# DP_current_measure_v2.net
KiCad netlist of a schematic drawn in EAGLE
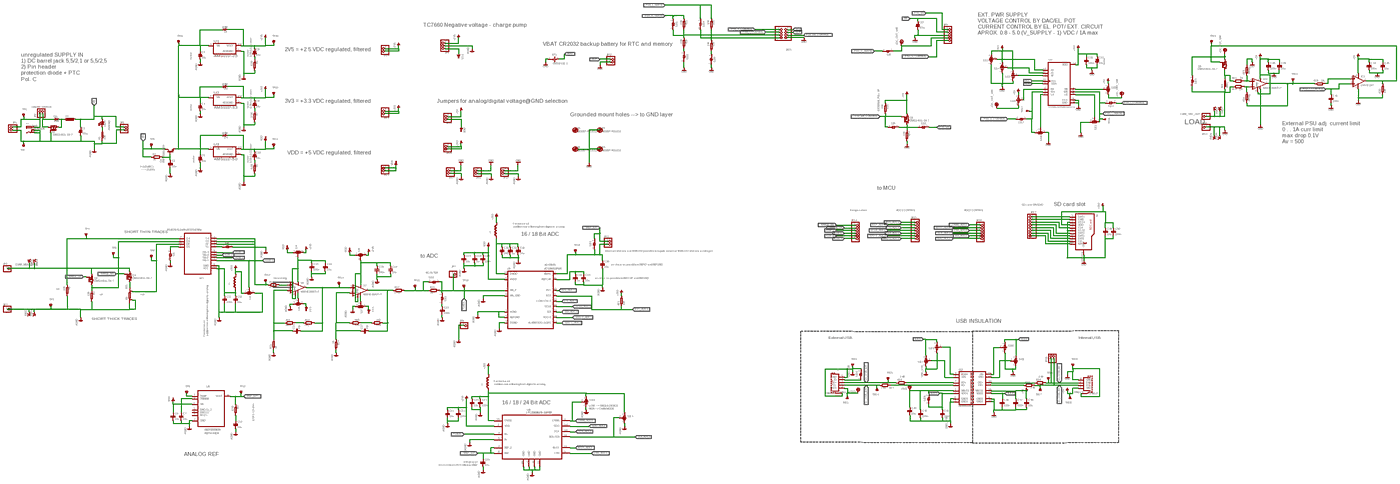
[diagram p0: schematic, sheet 1, overview]
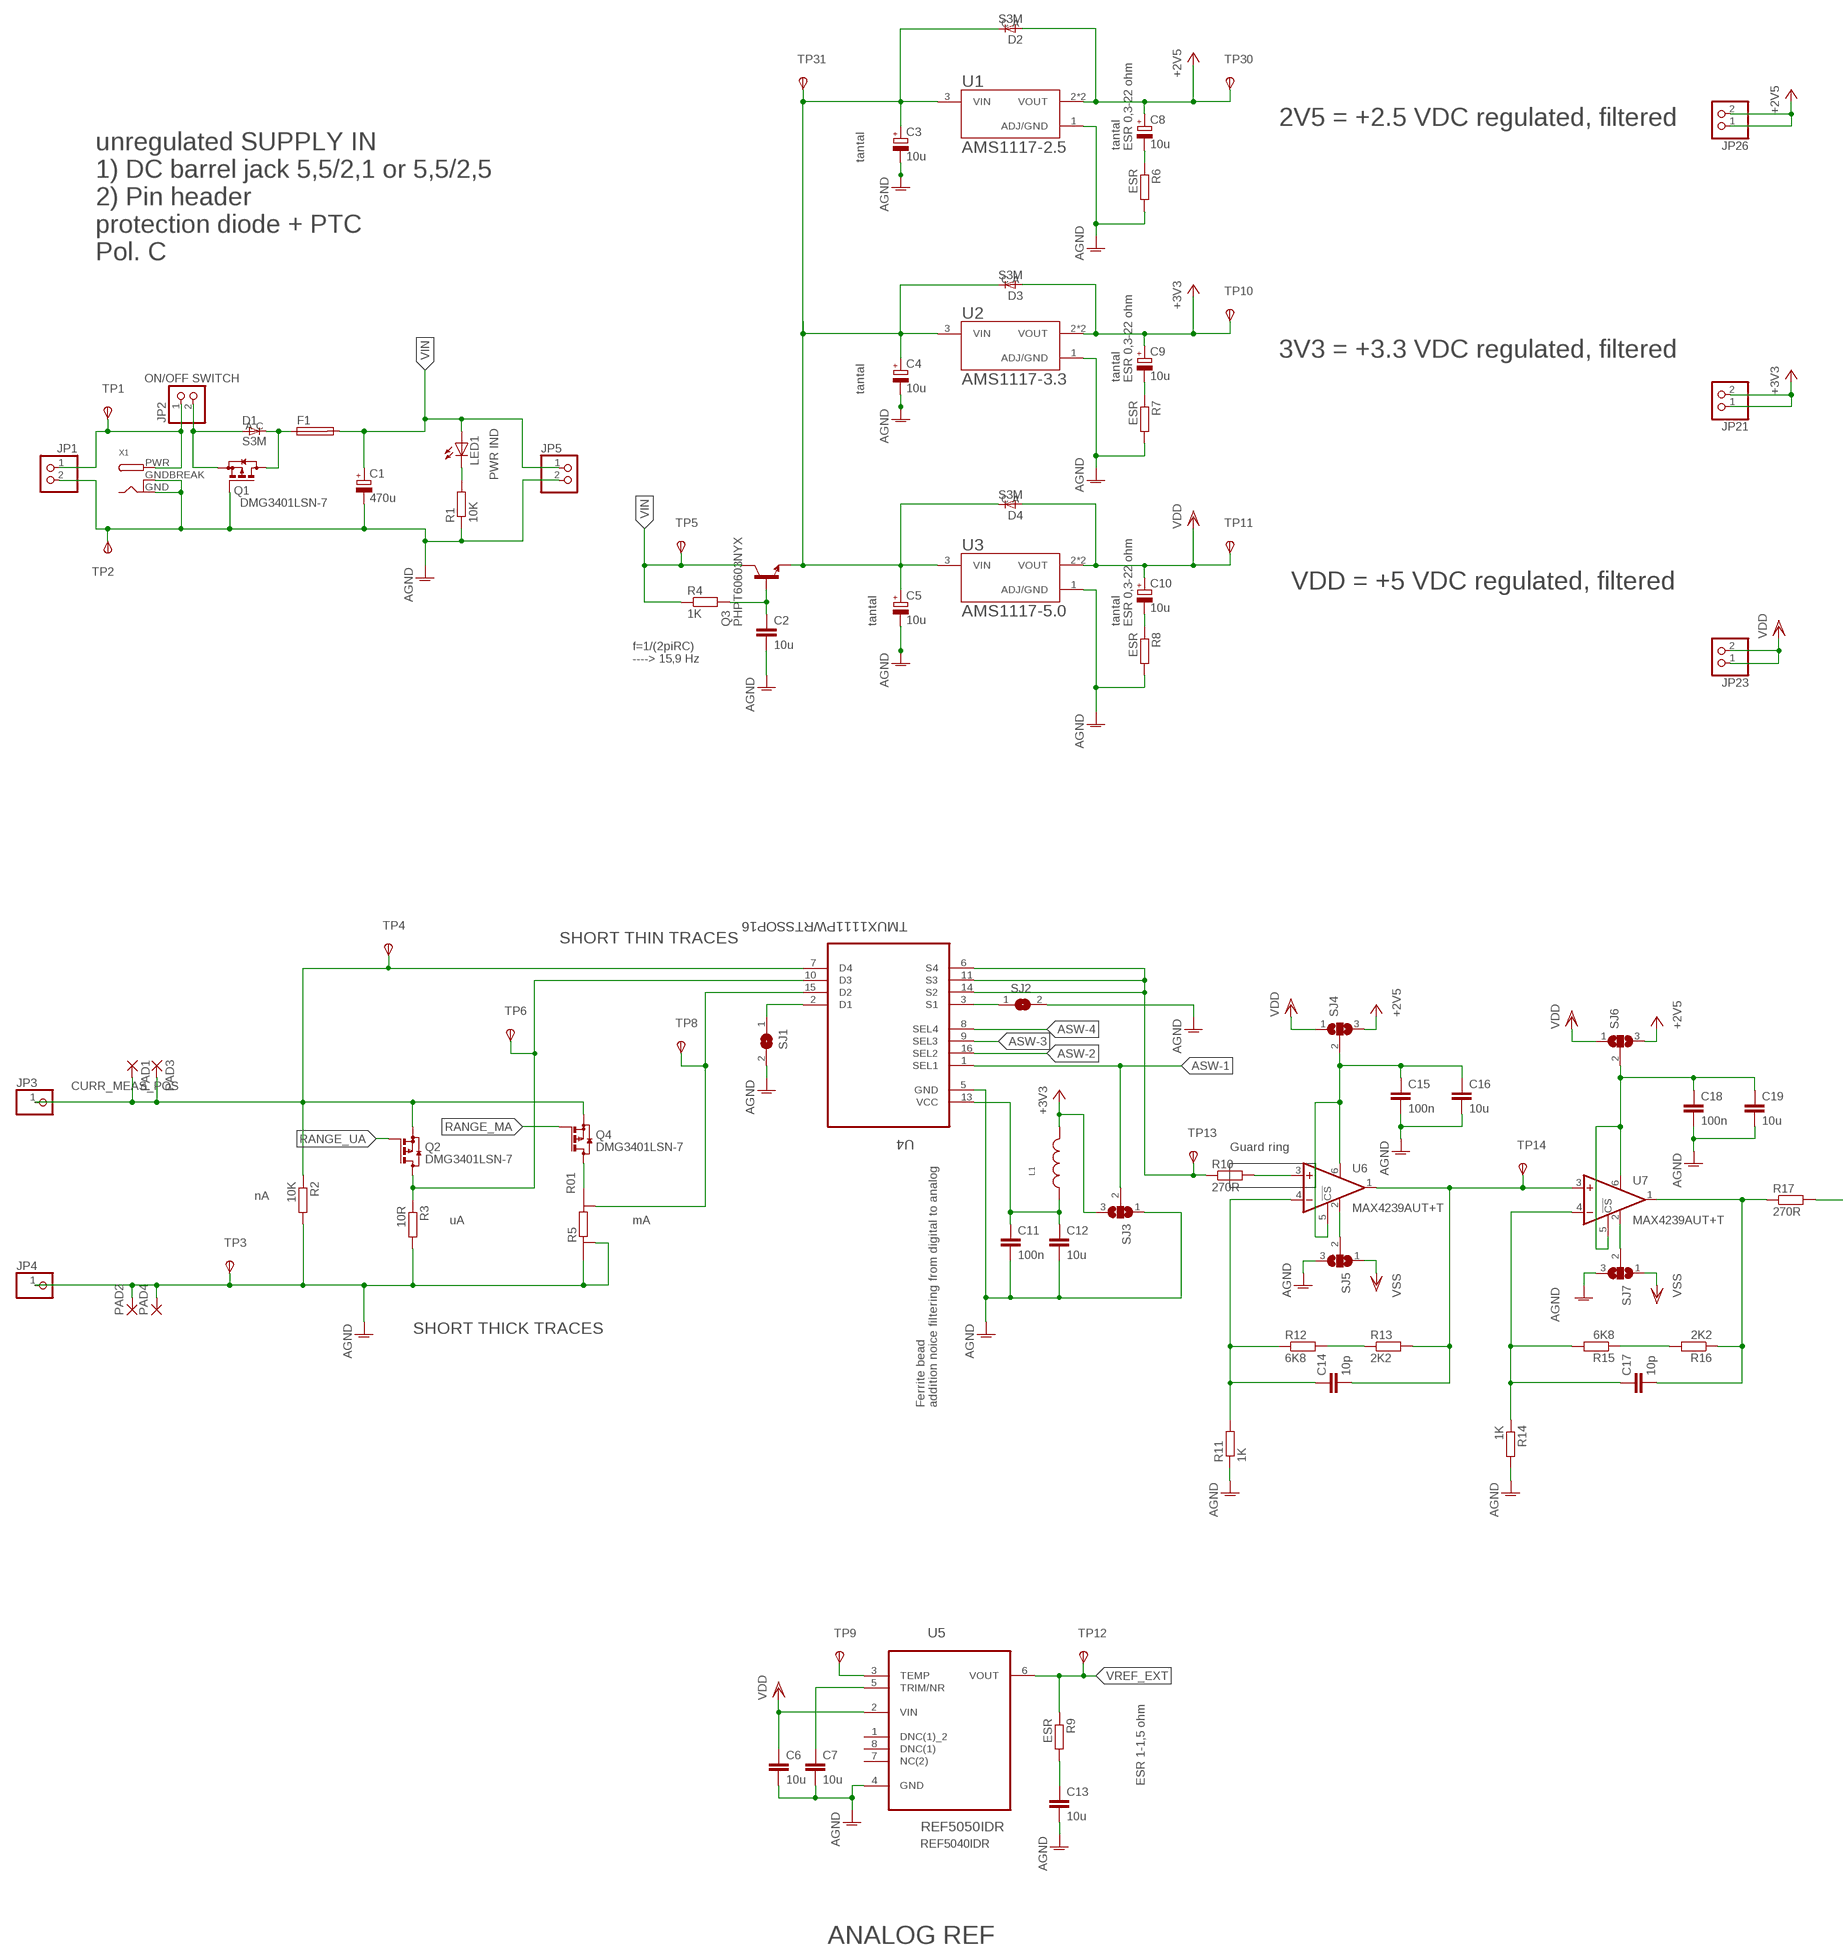
[diagram p1: schematic, sheet 1, part 1 of 4]
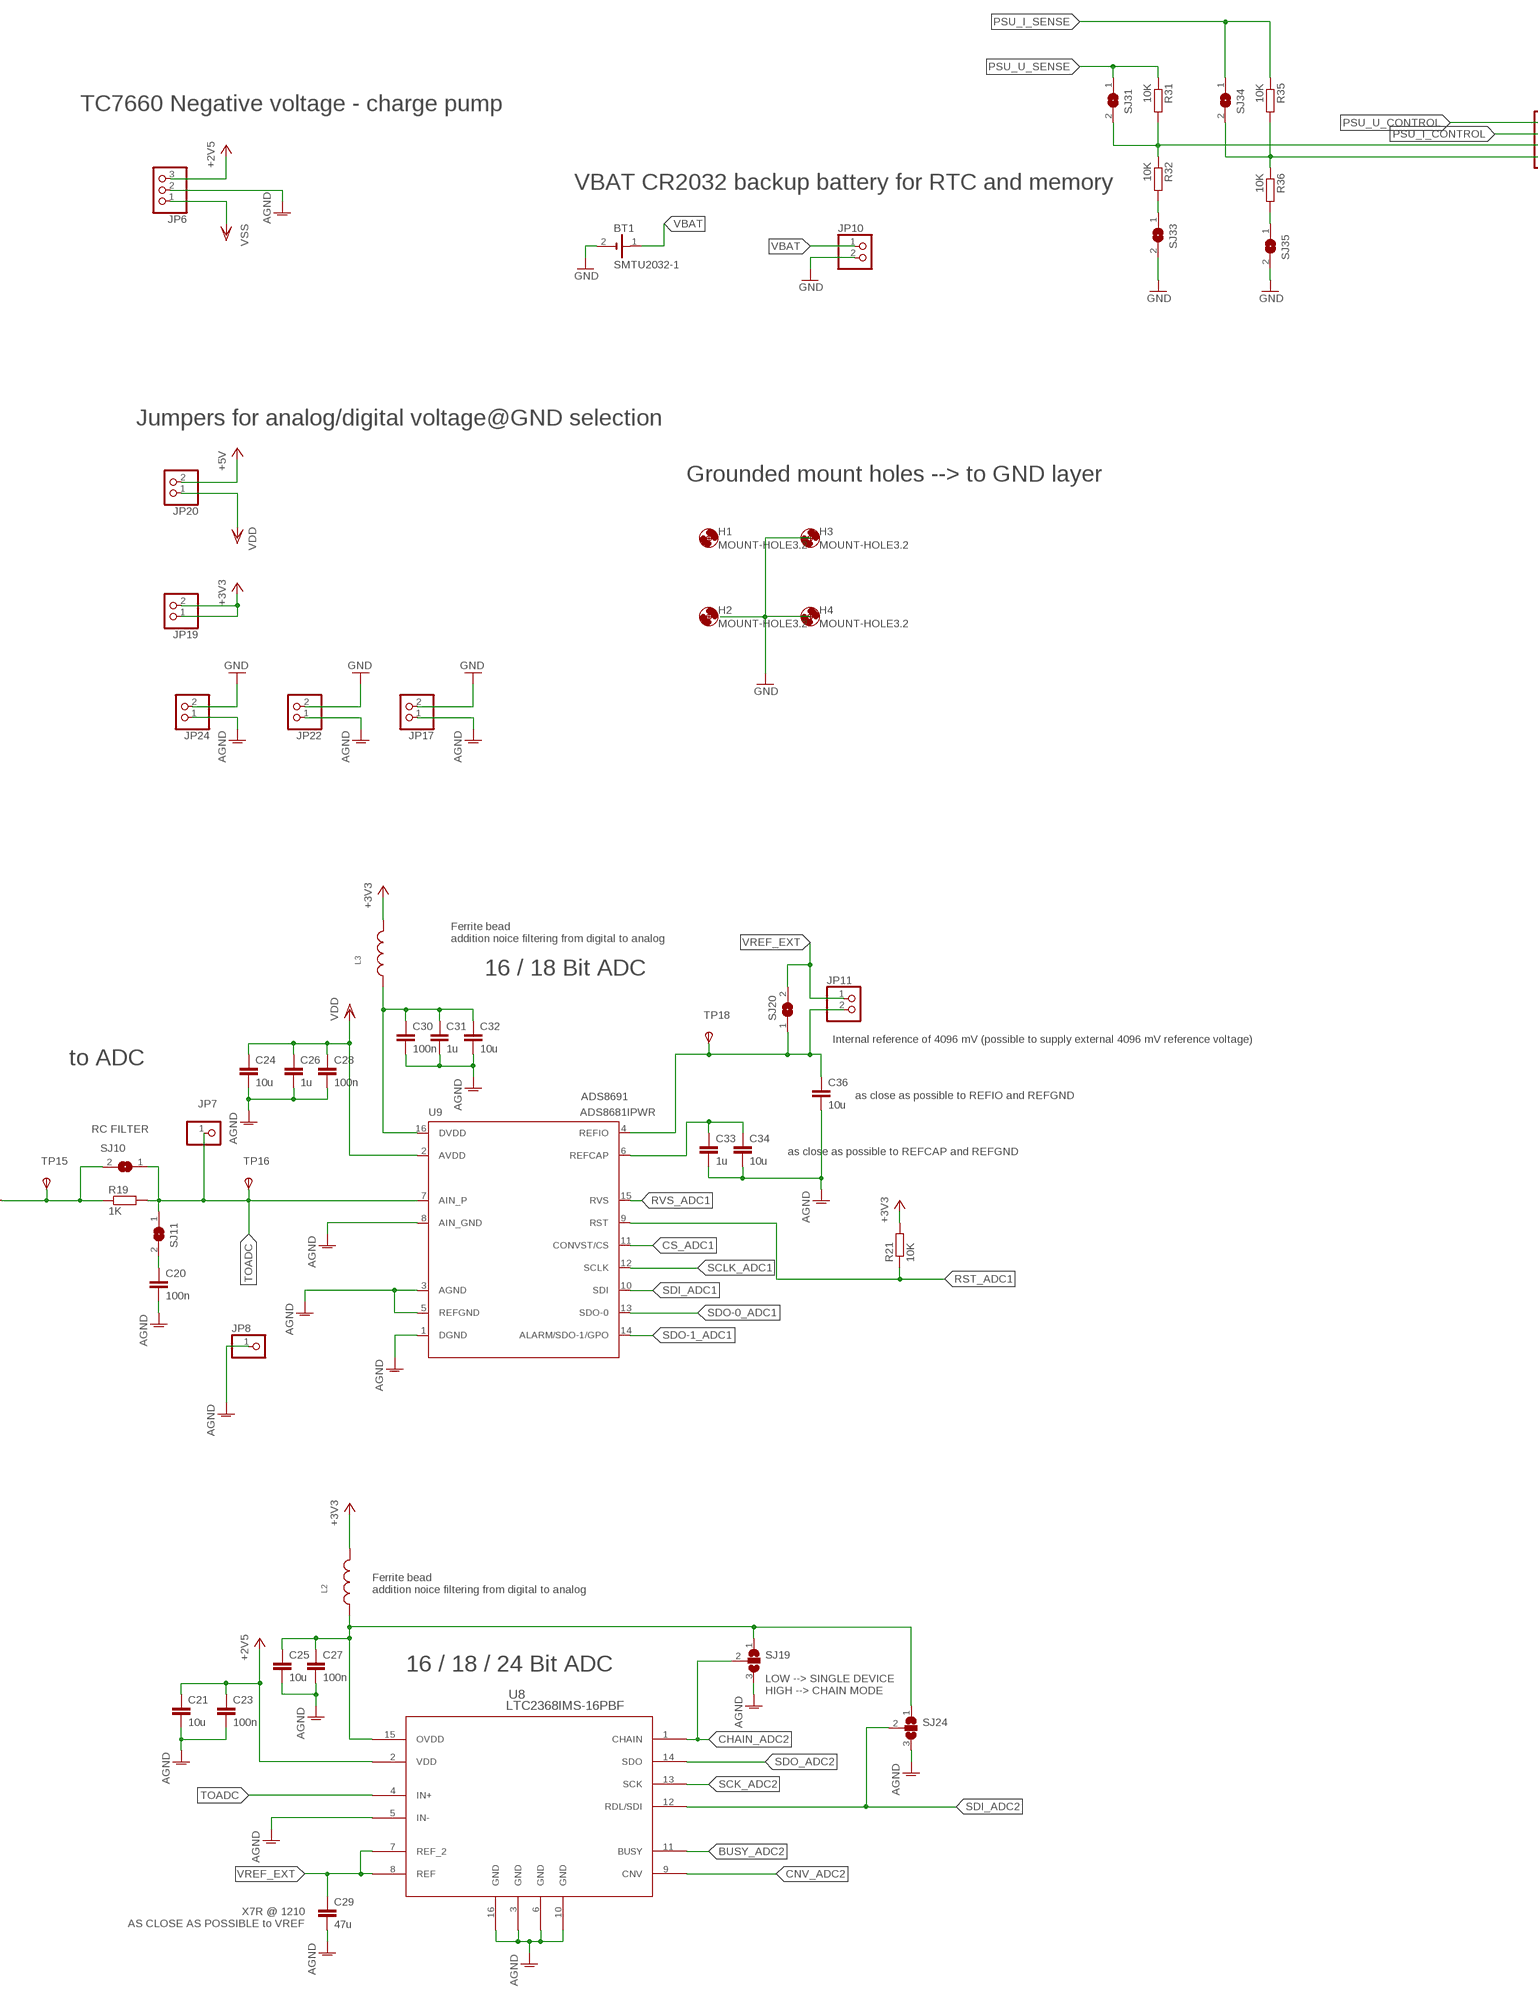
[diagram p2: schematic, sheet 1, part 2 of 4]
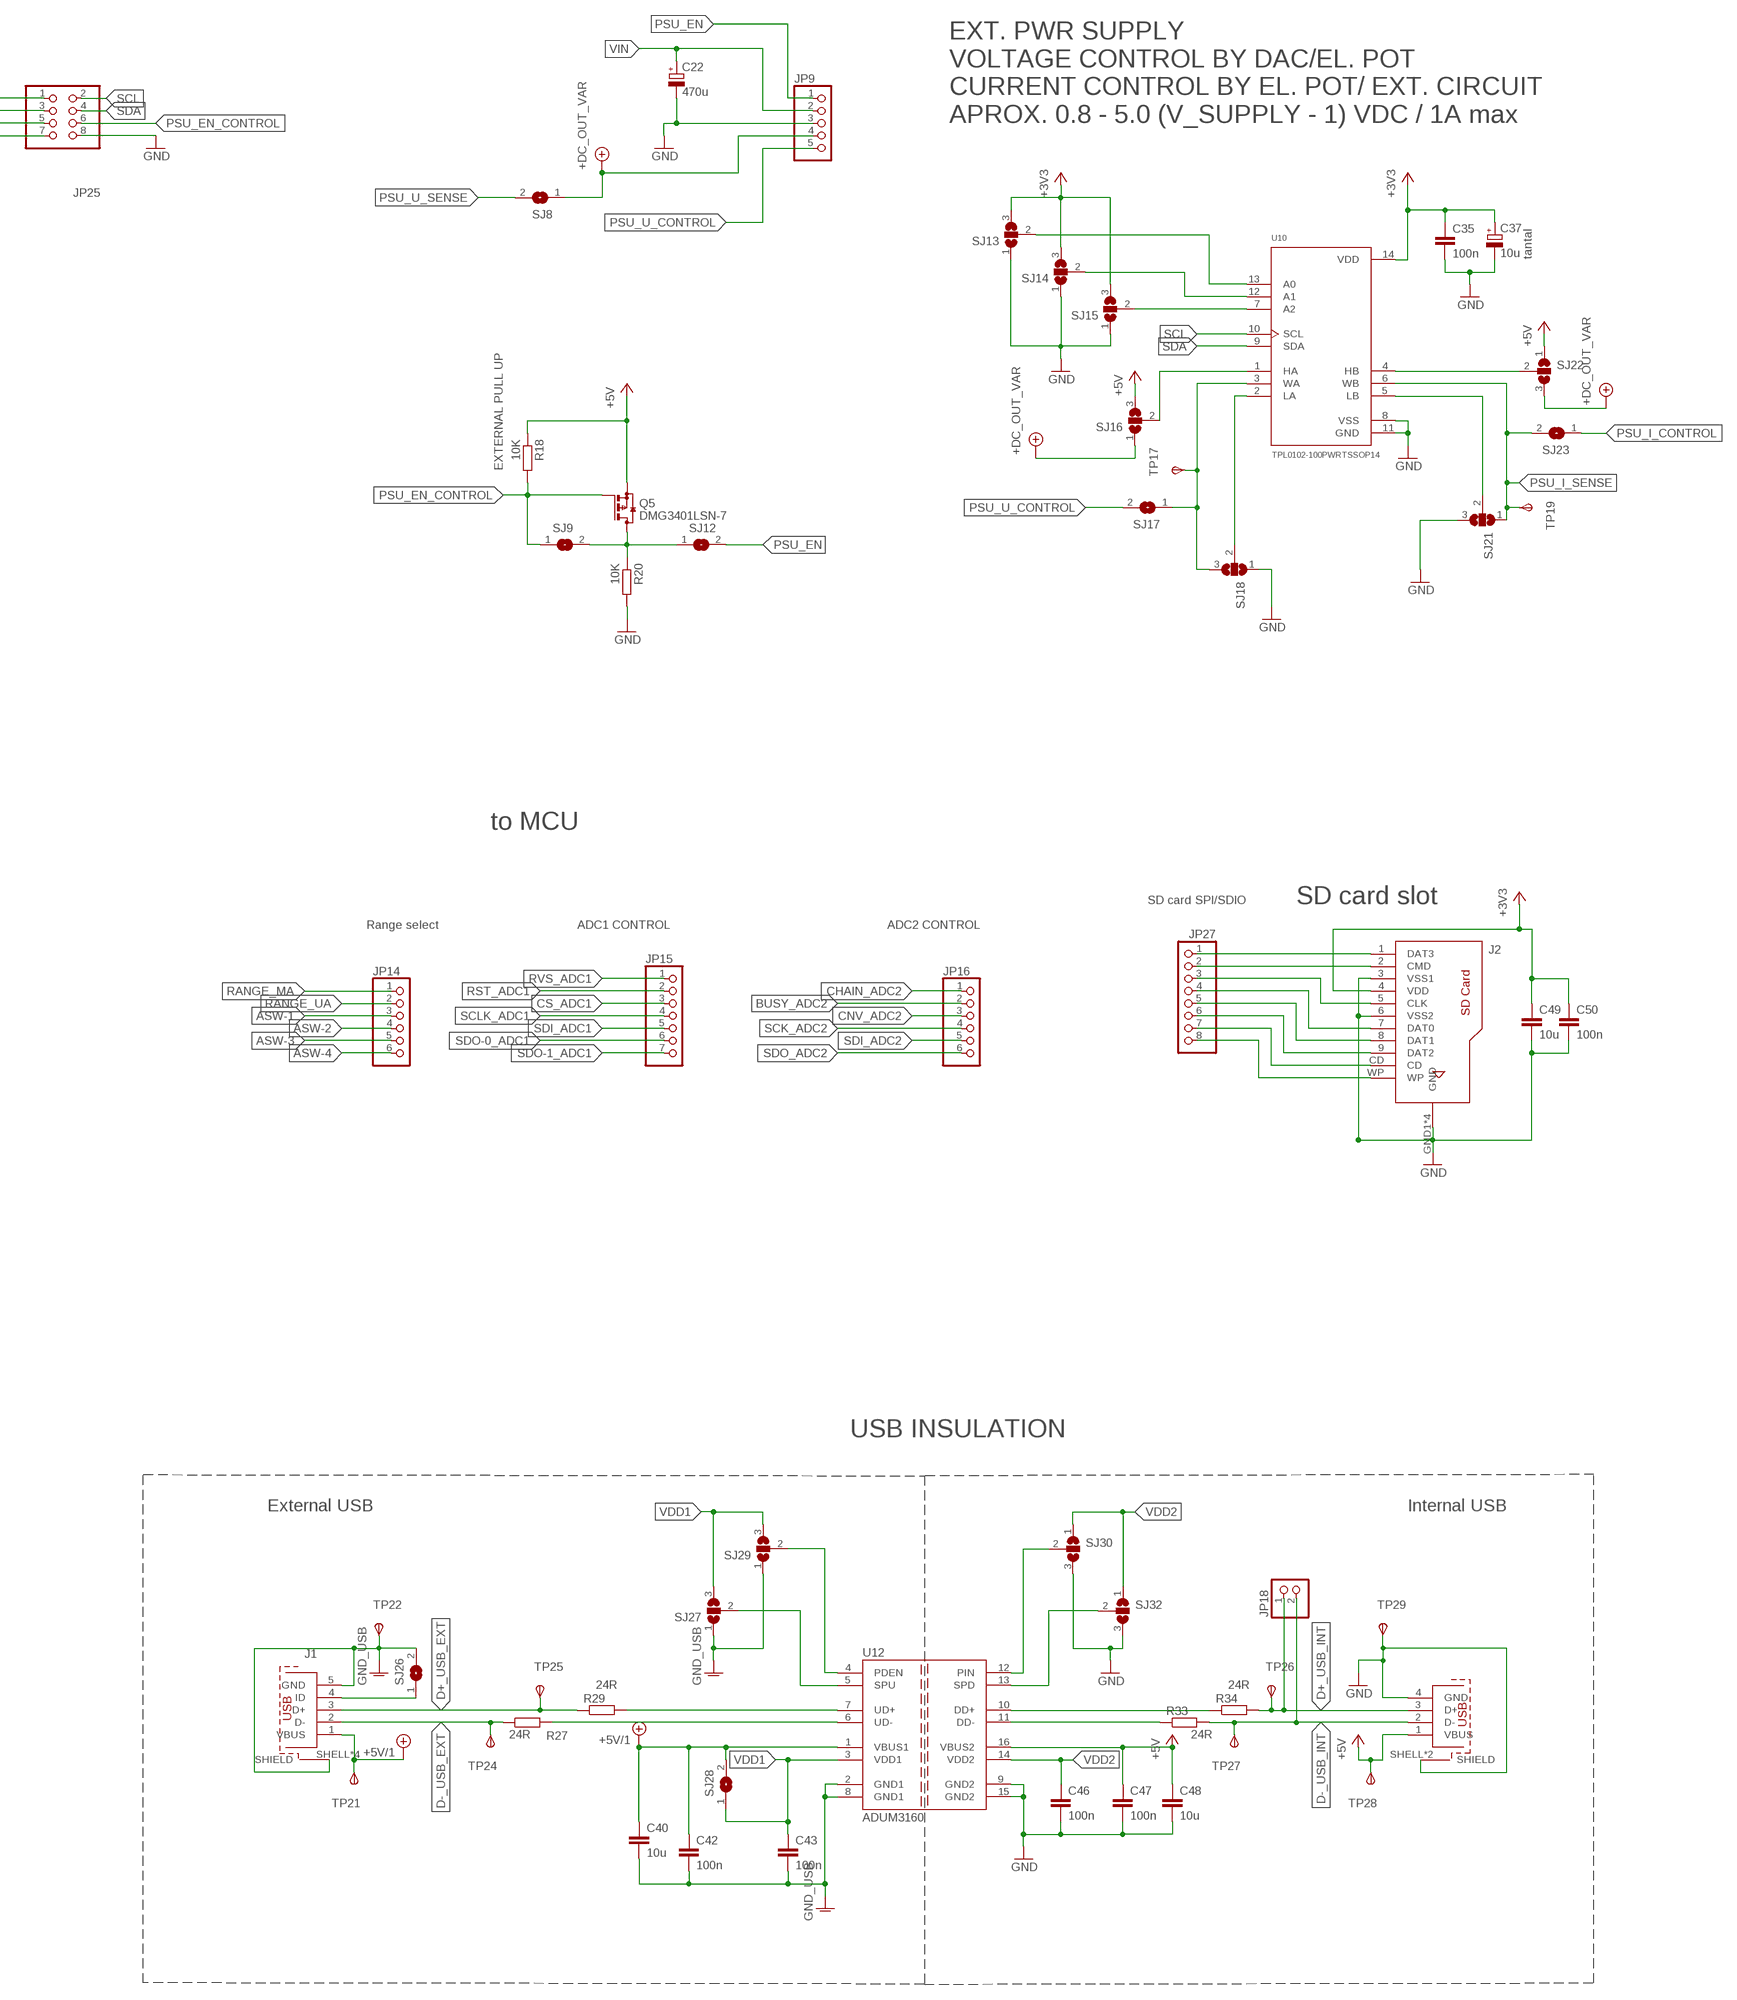
[diagram p3: schematic, sheet 1, part 3 of 4]
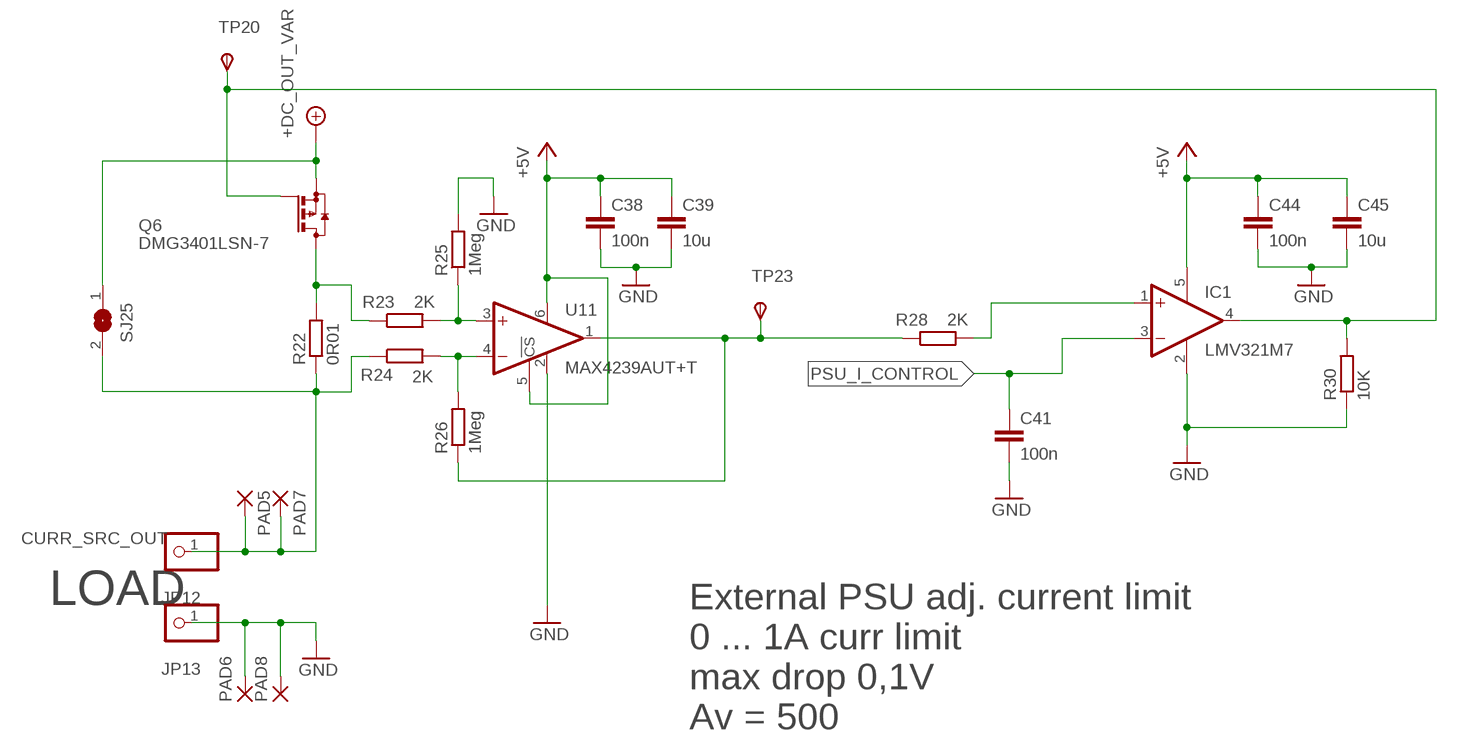
[diagram p4: schematic, sheet 1, part 4 of 4]

(export (version "E")
  (design (tool "Eeschema 10.0.6"))
  (components
    (comp (ref "BT1")
      (value "SMTU2032-1")
      (footprint "eagle-import:RENATA_SMTU2032-1")
      (fields (field (name "MF") "Renata"))
      (libsource (lib "eagle-import") (part "SMTU2032-1"))
    )
    (comp (ref "C1")
      (value "470u")
      (footprint "eagle-import:PANASONIC_G")
      (libsource (lib "eagle-import") (part "CPOL-EUG"))
    )
    (comp (ref "C2")
      (value "10u")
      (footprint "eagle-import:C1206")
      (libsource (lib "eagle-import") (part "C-EUC1206"))
    )
    (comp (ref "C3")
      (value "10u")
      (footprint "eagle-import:SMC_B")
      (libsource (lib "eagle-import") (part "CPOL-EUSMCB"))
    )
    (comp (ref "C4")
      (value "10u")
      (footprint "eagle-import:SMC_B")
      (libsource (lib "eagle-import") (part "CPOL-EUSMCB"))
    )
    (comp (ref "C5")
      (value "10u")
      (footprint "eagle-import:SMC_B")
      (libsource (lib "eagle-import") (part "CPOL-EUSMCB"))
    )
    (comp (ref "C6")
      (value "10u")
      (footprint "eagle-import:C1206")
      (libsource (lib "eagle-import") (part "C-EUC1206"))
    )
    (comp (ref "C7")
      (value "10u")
      (footprint "eagle-import:C1206")
      (libsource (lib "eagle-import") (part "C-EUC1206"))
    )
    (comp (ref "C8")
      (value "10u")
      (footprint "eagle-import:SMC_B")
      (libsource (lib "eagle-import") (part "CPOL-EUSMCB"))
    )
    (comp (ref "C9")
      (value "10u")
      (footprint "eagle-import:SMC_B")
      (libsource (lib "eagle-import") (part "CPOL-EUSMCB"))
    )
    (comp (ref "C10")
      (value "10u")
      (footprint "eagle-import:SMC_B")
      (libsource (lib "eagle-import") (part "CPOL-EUSMCB"))
    )
    (comp (ref "C11")
      (value "100n")
      (footprint "eagle-import:C0805")
      (libsource (lib "eagle-import") (part "C-EUC0805"))
    )
    (comp (ref "C12")
      (value "10u")
      (footprint "eagle-import:C1206")
      (libsource (lib "eagle-import") (part "C-EUC1206"))
    )
    (comp (ref "C13")
      (value "10u")
      (footprint "eagle-import:C1206")
      (libsource (lib "eagle-import") (part "C-EUC1206"))
    )
    (comp (ref "C14")
      (value "10p")
      (footprint "eagle-import:C0805")
      (libsource (lib "eagle-import") (part "C-EUC0805"))
    )
    (comp (ref "C15")
      (value "100n")
      (footprint "eagle-import:C0805")
      (libsource (lib "eagle-import") (part "C-EUC0805"))
    )
    (comp (ref "C16")
      (value "10u")
      (footprint "eagle-import:C1206")
      (libsource (lib "eagle-import") (part "C-EUC1206"))
    )
    (comp (ref "C17")
      (value "10p")
      (footprint "eagle-import:C0805")
      (libsource (lib "eagle-import") (part "C-EUC0805"))
    )
    (comp (ref "C18")
      (value "100n")
      (footprint "eagle-import:C0805")
      (libsource (lib "eagle-import") (part "C-EUC0805"))
    )
    (comp (ref "C19")
      (value "10u")
      (footprint "eagle-import:C1206")
      (libsource (lib "eagle-import") (part "C-EUC1206"))
    )
    (comp (ref "C20")
      (value "100n")
      (footprint "eagle-import:C1206")
      (libsource (lib "eagle-import") (part "C-EUC1206"))
    )
    (comp (ref "C21")
      (value "10u")
      (footprint "eagle-import:C1206")
      (libsource (lib "eagle-import") (part "C-EUC1206"))
    )
    (comp (ref "C22")
      (value "470u")
      (footprint "eagle-import:PANASONIC_G")
      (libsource (lib "eagle-import") (part "CPOL-EUG"))
    )
    (comp (ref "C23")
      (value "100n")
      (footprint "eagle-import:C0805")
      (libsource (lib "eagle-import") (part "C-EUC0805"))
    )
    (comp (ref "C24")
      (value "10u")
      (footprint "eagle-import:C1206")
      (libsource (lib "eagle-import") (part "C-EUC1206"))
    )
    (comp (ref "C25")
      (value "10u")
      (footprint "eagle-import:C1206")
      (libsource (lib "eagle-import") (part "C-EUC1206"))
    )
    (comp (ref "C26")
      (value "1u")
      (footprint "eagle-import:C0805")
      (libsource (lib "eagle-import") (part "C-EUC0805"))
    )
    (comp (ref "C27")
      (value "100n")
      (footprint "eagle-import:C0805")
      (libsource (lib "eagle-import") (part "C-EUC0805"))
    )
    (comp (ref "C28")
      (value "100n")
      (footprint "eagle-import:C0805")
      (libsource (lib "eagle-import") (part "C-EUC0805"))
    )
    (comp (ref "C29")
      (value "47u")
      (footprint "eagle-import:C1210")
      (libsource (lib "eagle-import") (part "C-EUC1210"))
    )
    (comp (ref "C30")
      (value "100n")
      (footprint "eagle-import:C0805")
      (libsource (lib "eagle-import") (part "C-EUC0805"))
    )
    (comp (ref "C31")
      (value "1u")
      (footprint "eagle-import:C0805")
      (libsource (lib "eagle-import") (part "C-EUC0805"))
    )
    (comp (ref "C32")
      (value "10u")
      (footprint "eagle-import:C1206")
      (libsource (lib "eagle-import") (part "C-EUC1206"))
    )
    (comp (ref "C33")
      (value "1u")
      (footprint "eagle-import:C0805")
      (libsource (lib "eagle-import") (part "C-EUC0805"))
    )
    (comp (ref "C34")
      (value "10u")
      (footprint "eagle-import:C1206")
      (libsource (lib "eagle-import") (part "C-EUC1206"))
    )
    (comp (ref "C35")
      (value "100n")
      (footprint "eagle-import:C0805")
      (libsource (lib "eagle-import") (part "C-EUC0805"))
    )
    (comp (ref "C36")
      (value "10u")
      (footprint "eagle-import:C1206")
      (libsource (lib "eagle-import") (part "C-EUC1206"))
    )
    (comp (ref "C37")
      (value "10u")
      (footprint "eagle-import:SMC_B")
      (libsource (lib "eagle-import") (part "CPOL-EUSMCB"))
    )
    (comp (ref "C38")
      (value "100n")
      (footprint "eagle-import:C0805")
      (libsource (lib "eagle-import") (part "C-EUC0805"))
    )
    (comp (ref "C39")
      (value "10u")
      (footprint "eagle-import:C1206")
      (libsource (lib "eagle-import") (part "C-EUC1206"))
    )
    (comp (ref "C40")
      (value "10u")
      (footprint "eagle-import:C1206")
      (libsource (lib "eagle-import") (part "C-EUC1206"))
    )
    (comp (ref "C41")
      (value "100n")
      (footprint "eagle-import:C0805")
      (libsource (lib "eagle-import") (part "C-EUC0805"))
    )
    (comp (ref "C42")
      (value "100n")
      (footprint "eagle-import:C0805")
      (libsource (lib "eagle-import") (part "C-EUC0805"))
    )
    (comp (ref "C43")
      (value "100n")
      (footprint "eagle-import:C0805")
      (libsource (lib "eagle-import") (part "C-EUC0805"))
    )
    (comp (ref "C44")
      (value "100n")
      (footprint "eagle-import:C0805")
      (libsource (lib "eagle-import") (part "C-EUC0805"))
    )
    (comp (ref "C45")
      (value "10u")
      (footprint "eagle-import:C1206")
      (libsource (lib "eagle-import") (part "C-EUC1206"))
    )
    (comp (ref "C46")
      (value "100n")
      (footprint "eagle-import:C0805")
      (libsource (lib "eagle-import") (part "C-EUC0805"))
    )
    (comp (ref "C47")
      (value "100n")
      (footprint "eagle-import:C0805")
      (libsource (lib "eagle-import") (part "C-EUC0805"))
    )
    (comp (ref "C48")
      (value "10u")
      (footprint "eagle-import:C1206")
      (libsource (lib "eagle-import") (part "C-EUC1206"))
    )
    (comp (ref "C49")
      (value "10u")
      (footprint "eagle-import:C1206")
      (libsource (lib "eagle-import") (part "C-EUC1206"))
    )
    (comp (ref "C50")
      (value "100n")
      (footprint "eagle-import:C0805")
      (libsource (lib "eagle-import") (part "C-EUC0805"))
    )
    (comp (ref "D1")
      (value "S3M")
      (footprint "eagle-import:DO214AC")
      (libsource (lib "eagle-import") (part "S1M"))
    )
    (comp (ref "D2")
      (value "S3M")
      (footprint "eagle-import:DO214AC")
      (libsource (lib "eagle-import") (part "S1M"))
    )
    (comp (ref "D3")
      (value "S3M")
      (footprint "eagle-import:DO214AC")
      (libsource (lib "eagle-import") (part "S1M"))
    )
    (comp (ref "D4")
      (value "S3M")
      (footprint "eagle-import:DO214AC")
      (libsource (lib "eagle-import") (part "S1M"))
    )
    (comp (ref "F1")
      (value "MF-MSMF050-2")
      (footprint "eagle-import:1812")
      (fields
        (field (name "DIGIKEY_PART_NUMBER") "MF-MSMF050-2TR-ND")
        (field (name "MANUFACTURER") "Bourns Inc.")
        (field (name "CREATED_BY") "PCBLayout.com")
      )
      (libsource (lib "eagle-import") (part "MF-MSMF050-2"))
    )
    (comp (ref "H1")
      (value "MOUNT-HOLE3.2")
      (footprint "eagle-import:3,2")
      (libsource (lib "eagle-import") (part "MOUNT-HOLE3.2"))
    )
    (comp (ref "H2")
      (value "MOUNT-HOLE3.2")
      (footprint "eagle-import:3,2")
      (libsource (lib "eagle-import") (part "MOUNT-HOLE3.2"))
    )
    (comp (ref "H3")
      (value "MOUNT-HOLE3.2")
      (footprint "eagle-import:3,2")
      (libsource (lib "eagle-import") (part "MOUNT-HOLE3.2"))
    )
    (comp (ref "H4")
      (value "MOUNT-HOLE3.2")
      (footprint "eagle-import:3,2")
      (libsource (lib "eagle-import") (part "MOUNT-HOLE3.2"))
    )
    (comp (ref "IC1")
      (value "LMV321M7")
      (footprint "eagle-import:SC70-5L")
      (libsource (lib "eagle-import") (part "LMV321?M7"))
    )
    (comp (ref "J1")
      (value "629105150521")
      (footprint "eagle-import:629105150521")
      (libsource (lib "eagle-import") (part "629105150521"))
    )
    (comp (ref "J2")
      (value "693063020911")
      (footprint "eagle-import:693063020911")
      (libsource (lib "eagle-import") (part "693063020911"))
    )
    (comp (ref "J3")
      (value "614004185023")
      (footprint "eagle-import:614004185023")
      (libsource (lib "eagle-import") (part "614004185023"))
    )
    (comp (ref "JP1")
      (value "PINHD-1X2")
      (footprint "eagle-import:1X02")
      (libsource (lib "eagle-import") (part "PINHD-1X2"))
    )
    (comp (ref "JP2")
      (value "PINHD-1X2")
      (footprint "eagle-import:1X02")
      (libsource (lib "eagle-import") (part "PINHD-1X2"))
    )
    (comp (ref "JP3")
      (value "PINHD-1X1")
      (footprint "eagle-import:1X01")
      (libsource (lib "eagle-import") (part "PINHD-1X1"))
    )
    (comp (ref "JP4")
      (value "PINHD-1X1")
      (footprint "eagle-import:1X01")
      (libsource (lib "eagle-import") (part "PINHD-1X1"))
    )
    (comp (ref "JP5")
      (value "PINHD-1X2")
      (footprint "eagle-import:1X02")
      (libsource (lib "eagle-import") (part "PINHD-1X2"))
    )
    (comp (ref "JP6")
      (value "PINHD-1X3")
      (footprint "eagle-import:1X03")
      (libsource (lib "eagle-import") (part "PINHD-1X3"))
    )
    (comp (ref "JP7")
      (value "PINHD-1X1")
      (footprint "eagle-import:1X01")
      (libsource (lib "eagle-import") (part "PINHD-1X1"))
    )
    (comp (ref "JP8")
      (value "PINHD-1X1")
      (footprint "eagle-import:1X01")
      (libsource (lib "eagle-import") (part "PINHD-1X1"))
    )
    (comp (ref "JP9")
      (value "PSU_STEP_DOWN")
      (footprint "eagle-import:1X05")
      (libsource (lib "eagle-import") (part "PSU_STEP_DOWN"))
    )
    (comp (ref "JP10")
      (value "PINHD-1X2")
      (footprint "eagle-import:1X02")
      (libsource (lib "eagle-import") (part "PINHD-1X2"))
    )
    (comp (ref "JP11")
      (value "PINHD-1X2")
      (footprint "eagle-import:1X02")
      (libsource (lib "eagle-import") (part "PINHD-1X2"))
    )
    (comp (ref "JP12")
      (value "PINHD-1X1")
      (footprint "eagle-import:1X01")
      (libsource (lib "eagle-import") (part "PINHD-1X1"))
    )
    (comp (ref "JP13")
      (value "PINHD-1X1")
      (footprint "eagle-import:1X01")
      (libsource (lib "eagle-import") (part "PINHD-1X1"))
    )
    (comp (ref "JP14")
      (value "PINHD-1X6")
      (footprint "eagle-import:1X06")
      (libsource (lib "eagle-import") (part "PINHD-1X6"))
    )
    (comp (ref "JP15")
      (value "PINHD-1X7")
      (footprint "eagle-import:1X07")
      (libsource (lib "eagle-import") (part "PINHD-1X7"))
    )
    (comp (ref "JP16")
      (value "PINHD-1X6")
      (footprint "eagle-import:1X06")
      (libsource (lib "eagle-import") (part "PINHD-1X6"))
    )
    (comp (ref "JP17")
      (value "PINHD-1X2")
      (footprint "eagle-import:1X02")
      (libsource (lib "eagle-import") (part "PINHD-1X2"))
    )
    (comp (ref "JP18")
      (value "PINHD-1X2")
      (footprint "eagle-import:1X02")
      (libsource (lib "eagle-import") (part "PINHD-1X2"))
    )
    (comp (ref "JP19")
      (value "PINHD-1X2")
      (footprint "eagle-import:1X02")
      (libsource (lib "eagle-import") (part "PINHD-1X2"))
    )
    (comp (ref "JP20")
      (value "PINHD-1X2")
      (footprint "eagle-import:1X02")
      (libsource (lib "eagle-import") (part "PINHD-1X2"))
    )
    (comp (ref "JP21")
      (value "PINHD-1X2")
      (footprint "eagle-import:1X02")
      (libsource (lib "eagle-import") (part "PINHD-1X2"))
    )
    (comp (ref "JP22")
      (value "PINHD-1X2")
      (footprint "eagle-import:1X02")
      (libsource (lib "eagle-import") (part "PINHD-1X2"))
    )
    (comp (ref "JP23")
      (value "PINHD-1X2")
      (footprint "eagle-import:1X02")
      (libsource (lib "eagle-import") (part "PINHD-1X2"))
    )
    (comp (ref "JP24")
      (value "PINHD-1X2")
      (footprint "eagle-import:1X02")
      (libsource (lib "eagle-import") (part "PINHD-1X2"))
    )
    (comp (ref "JP25")
      (value "PINHD-2X4")
      (footprint "eagle-import:2X04")
      (libsource (lib "eagle-import") (part "PINHD-2X4"))
    )
    (comp (ref "JP26")
      (value "PINHD-1X2")
      (footprint "eagle-import:1X02")
      (libsource (lib "eagle-import") (part "PINHD-1X2"))
    )
    (comp (ref "JP27")
      (value "PINHD-1X8")
      (footprint "eagle-import:1X08")
      (libsource (lib "eagle-import") (part "PINHD-1X8"))
    )
    (comp (ref "L1")
      (value "WE-CBF_0805_742792036_WB_HS")
      (footprint "eagle-import:WE-CBF_0805(W=3.0)")
      (libsource (lib "eagle-import") (part "WE-CBF_0805_WB_HS_742792036"))
    )
    (comp (ref "L2")
      (value "WE-CBF_0805_742792036_WB_HS")
      (footprint "eagle-import:WE-CBF_0805(W=3.0)")
      (libsource (lib "eagle-import") (part "WE-CBF_0805_WB_HS_742792036"))
    )
    (comp (ref "L3")
      (value "WE-CBF_0805_742792036_WB_HS")
      (footprint "eagle-import:WE-CBF_0805(W=3.0)")
      (libsource (lib "eagle-import") (part "WE-CBF_0805_WB_HS_742792036"))
    )
    (comp (ref "LED1")
      (value "LEDCHIPLED_0805")
      (footprint "eagle-import:CHIPLED_0805")
      (libsource (lib "eagle-import") (part "LEDCHIPLED_0805"))
    )
    (comp (ref "PAD1")
      (value "WIREPADSMD2,54-5,08")
      (footprint "eagle-import:SMD2,54-5,08")
      (libsource (lib "eagle-import") (part "WIREPADSMD2,54-5,08"))
    )
    (comp (ref "PAD2")
      (value "WIREPADSMD2,54-5,08")
      (footprint "eagle-import:SMD2,54-5,08")
      (libsource (lib "eagle-import") (part "WIREPADSMD2,54-5,08"))
    )
    (comp (ref "PAD3")
      (value "WIREPADSMD2,54-5,08")
      (footprint "eagle-import:SMD2,54-5,08")
      (libsource (lib "eagle-import") (part "WIREPADSMD2,54-5,08"))
    )
    (comp (ref "PAD4")
      (value "WIREPADSMD2,54-5,08")
      (footprint "eagle-import:SMD2,54-5,08")
      (libsource (lib "eagle-import") (part "WIREPADSMD2,54-5,08"))
    )
    (comp (ref "PAD5")
      (value "WIREPADSMD2,54-5,08")
      (footprint "eagle-import:SMD2,54-5,08")
      (libsource (lib "eagle-import") (part "WIREPADSMD2,54-5,08"))
    )
    (comp (ref "PAD6")
      (value "WIREPADSMD2,54-5,08")
      (footprint "eagle-import:SMD2,54-5,08")
      (libsource (lib "eagle-import") (part "WIREPADSMD2,54-5,08"))
    )
    (comp (ref "PAD7")
      (value "WIREPADSMD2,54-5,08")
      (footprint "eagle-import:SMD2,54-5,08")
      (libsource (lib "eagle-import") (part "WIREPADSMD2,54-5,08"))
    )
    (comp (ref "PAD8")
      (value "WIREPADSMD2,54-5,08")
      (footprint "eagle-import:SMD2,54-5,08")
      (libsource (lib "eagle-import") (part "WIREPADSMD2,54-5,08"))
    )
    (comp (ref "Q1")
      (value "DMG3401LSN-7")
      (footprint "eagle-import:SOT23")
      (libsource (lib "eagle-import") (part "DMG3401LSN-7"))
    )
    (comp (ref "Q2")
      (value "DMG3401LSN-7")
      (footprint "eagle-import:SOT23")
      (libsource (lib "eagle-import") (part "DMG3401LSN-7"))
    )
    (comp (ref "Q3")
      (value "PHPT60603NYX")
      (footprint "eagle-import:TO127P600X120-5N")
      (libsource (lib "eagle-import") (part "PHPT60603NYX"))
    )
    (comp (ref "Q4")
      (value "DMG3401LSN-7")
      (footprint "eagle-import:SOT23")
      (libsource (lib "eagle-import") (part "DMG3401LSN-7"))
    )
    (comp (ref "Q5")
      (value "DMG3401LSN-7")
      (footprint "eagle-import:SOT23")
      (libsource (lib "eagle-import") (part "DMG3401LSN-7"))
    )
    (comp (ref "Q6")
      (value "DMG3401LSN-7")
      (footprint "eagle-import:SOT23")
      (libsource (lib "eagle-import") (part "DMG3401LSN-7"))
    )
    (comp (ref "R1")
      (value "10K")
      (footprint "eagle-import:R0805")
      (libsource (lib "eagle-import") (part "R-EU_R0805"))
    )
    (comp (ref "R2")
      (value "10K")
      (footprint "eagle-import:R0805")
      (libsource (lib "eagle-import") (part "R-EU_R0805"))
    )
    (comp (ref "R3")
      (value "10R")
      (footprint "eagle-import:R0805")
      (libsource (lib "eagle-import") (part "R-EU_R0805"))
    )
    (comp (ref "R4")
      (value "1K")
      (footprint "eagle-import:R0805")
      (libsource (lib "eagle-import") (part "R-EU_R0805"))
    )
    (comp (ref "R5")
      (value "R01")
      (footprint "eagle-import:R2512")
      (libsource (lib "eagle-import") (part "CSM_R01"))
    )
    (comp (ref "R6")
      (value "ESR")
      (footprint "eagle-import:R0805")
      (libsource (lib "eagle-import") (part "R-EU_R0805"))
    )
    (comp (ref "R7")
      (value "ESR")
      (footprint "eagle-import:R0805")
      (libsource (lib "eagle-import") (part "R-EU_R0805"))
    )
    (comp (ref "R8")
      (value "ESR")
      (footprint "eagle-import:R0805")
      (libsource (lib "eagle-import") (part "R-EU_R0805"))
    )
    (comp (ref "R9")
      (value "ESR")
      (footprint "eagle-import:R0805")
      (libsource (lib "eagle-import") (part "R-EU_R0805"))
    )
    (comp (ref "R10")
      (value "270R")
      (footprint "eagle-import:R0805")
      (libsource (lib "eagle-import") (part "R-EU_R0805"))
    )
    (comp (ref "R11")
      (value "1K")
      (footprint "eagle-import:R0805")
      (libsource (lib "eagle-import") (part "R-EU_R0805"))
    )
    (comp (ref "R12")
      (value "6K8")
      (footprint "eagle-import:R0805")
      (libsource (lib "eagle-import") (part "R-EU_R0805"))
    )
    (comp (ref "R13")
      (value "2K2")
      (footprint "eagle-import:R0805")
      (libsource (lib "eagle-import") (part "R-EU_R0805"))
    )
    (comp (ref "R14")
      (value "1K")
      (footprint "eagle-import:R0805")
      (libsource (lib "eagle-import") (part "R-EU_R0805"))
    )
    (comp (ref "R15")
      (value "6K8")
      (footprint "eagle-import:R0805")
      (libsource (lib "eagle-import") (part "R-EU_R0805"))
    )
    (comp (ref "R16")
      (value "2K2")
      (footprint "eagle-import:R0805")
      (libsource (lib "eagle-import") (part "R-EU_R0805"))
    )
    (comp (ref "R17")
      (value "270R")
      (footprint "eagle-import:R0805")
      (libsource (lib "eagle-import") (part "R-EU_R0805"))
    )
    (comp (ref "R18")
      (value "10K")
      (footprint "eagle-import:R0805")
      (libsource (lib "eagle-import") (part "R-EU_R0805"))
    )
    (comp (ref "R19")
      (value "1K")
      (footprint "eagle-import:R0805")
      (libsource (lib "eagle-import") (part "R-EU_R0805"))
    )
    (comp (ref "R20")
      (value "10K")
      (footprint "eagle-import:R0805")
      (libsource (lib "eagle-import") (part "R-EU_R0805"))
    )
    (comp (ref "R21")
      (value "10K")
      (footprint "eagle-import:R0805")
      (libsource (lib "eagle-import") (part "R-EU_R0805"))
    )
    (comp (ref "R22")
      (value "0R01")
      (footprint "eagle-import:R0805")
      (libsource (lib "eagle-import") (part "R-EU_R0805"))
    )
    (comp (ref "R23")
      (value "2K")
      (footprint "eagle-import:R0805")
      (libsource (lib "eagle-import") (part "R-EU_R0805"))
    )
    (comp (ref "R24")
      (value "2K")
      (footprint "eagle-import:R0805")
      (libsource (lib "eagle-import") (part "R-EU_R0805"))
    )
    (comp (ref "R25")
      (value "1Meg")
      (footprint "eagle-import:R0805")
      (libsource (lib "eagle-import") (part "R-EU_R0805"))
    )
    (comp (ref "R26")
      (value "1Meg")
      (footprint "eagle-import:R0805")
      (libsource (lib "eagle-import") (part "R-EU_R0805"))
    )
    (comp (ref "R27")
      (value "24R")
      (footprint "eagle-import:R0805")
      (libsource (lib "eagle-import") (part "R-EU_R0805"))
    )
    (comp (ref "R28")
      (value "2K")
      (footprint "eagle-import:R0805")
      (libsource (lib "eagle-import") (part "R-EU_R0805"))
    )
    (comp (ref "R29")
      (value "24R")
      (footprint "eagle-import:R0805")
      (libsource (lib "eagle-import") (part "R-EU_R0805"))
    )
    (comp (ref "R30")
      (value "10K")
      (footprint "eagle-import:R0805")
      (libsource (lib "eagle-import") (part "R-EU_R0805"))
    )
    (comp (ref "R31")
      (value "10K")
      (footprint "eagle-import:R0805")
      (libsource (lib "eagle-import") (part "R-EU_R0805"))
    )
    (comp (ref "R32")
      (value "10K")
      (footprint "eagle-import:R0805")
      (libsource (lib "eagle-import") (part "R-EU_R0805"))
    )
    (comp (ref "R33")
      (value "24R")
      (footprint "eagle-import:R0805")
      (libsource (lib "eagle-import") (part "R-EU_R0805"))
    )
    (comp (ref "R34")
      (value "24R")
      (footprint "eagle-import:R0805")
      (libsource (lib "eagle-import") (part "R-EU_R0805"))
    )
    (comp (ref "R35")
      (value "10K")
      (footprint "eagle-import:R0805")
      (libsource (lib "eagle-import") (part "R-EU_R0805"))
    )
    (comp (ref "R36")
      (value "10K")
      (footprint "eagle-import:R0805")
      (libsource (lib "eagle-import") (part "R-EU_R0805"))
    )
    (comp (ref "SJ1") (value "SJ") (footprint "eagle-import:SJ") (libsource (lib "eagle-import") (part "SJ")))
    (comp (ref "SJ2") (value "SJ") (footprint "eagle-import:SJ") (libsource (lib "eagle-import") (part "SJ")))
    (comp (ref "SJ3")
      (value "SJ2W")
      (footprint "eagle-import:SJ_2")
      (libsource (lib "eagle-import") (part "SJ2W"))
    )
    (comp (ref "SJ4")
      (value "SJ2W")
      (footprint "eagle-import:SJ_2")
      (libsource (lib "eagle-import") (part "SJ2W"))
    )
    (comp (ref "SJ5")
      (value "SJ2W")
      (footprint "eagle-import:SJ_2")
      (libsource (lib "eagle-import") (part "SJ2W"))
    )
    (comp (ref "SJ6")
      (value "SJ2W")
      (footprint "eagle-import:SJ_2")
      (libsource (lib "eagle-import") (part "SJ2W"))
    )
    (comp (ref "SJ7")
      (value "SJ2W")
      (footprint "eagle-import:SJ_2")
      (libsource (lib "eagle-import") (part "SJ2W"))
    )
    (comp (ref "SJ8") (value "SJ") (footprint "eagle-import:SJ") (libsource (lib "eagle-import") (part "SJ")))
    (comp (ref "SJ9") (value "SJ") (footprint "eagle-import:SJ") (libsource (lib "eagle-import") (part "SJ")))
    (comp (ref "SJ10")
      (value "SJ")
      (footprint "eagle-import:SJ")
      (libsource (lib "eagle-import") (part "SJ"))
    )
    (comp (ref "SJ11")
      (value "SJ")
      (footprint "eagle-import:SJ")
      (libsource (lib "eagle-import") (part "SJ"))
    )
    (comp (ref "SJ12")
      (value "SJ")
      (footprint "eagle-import:SJ")
      (libsource (lib "eagle-import") (part "SJ"))
    )
    (comp (ref "SJ13")
      (value "SJ2W")
      (footprint "eagle-import:SJ_2")
      (libsource (lib "eagle-import") (part "SJ2W"))
    )
    (comp (ref "SJ14")
      (value "SJ2W")
      (footprint "eagle-import:SJ_2")
      (libsource (lib "eagle-import") (part "SJ2W"))
    )
    (comp (ref "SJ15")
      (value "SJ2W")
      (footprint "eagle-import:SJ_2")
      (libsource (lib "eagle-import") (part "SJ2W"))
    )
    (comp (ref "SJ16")
      (value "SJ2W")
      (footprint "eagle-import:SJ_2")
      (libsource (lib "eagle-import") (part "SJ2W"))
    )
    (comp (ref "SJ17")
      (value "SJ")
      (footprint "eagle-import:SJ")
      (libsource (lib "eagle-import") (part "SJ"))
    )
    (comp (ref "SJ18")
      (value "SJ2W")
      (footprint "eagle-import:SJ_2")
      (libsource (lib "eagle-import") (part "SJ2W"))
    )
    (comp (ref "SJ19")
      (value "SJ2W")
      (footprint "eagle-import:SJ_2")
      (libsource (lib "eagle-import") (part "SJ2W"))
    )
    (comp (ref "SJ20")
      (value "SJ")
      (footprint "eagle-import:SJ")
      (libsource (lib "eagle-import") (part "SJ"))
    )
    (comp (ref "SJ21")
      (value "SJ2W")
      (footprint "eagle-import:SJ_2")
      (libsource (lib "eagle-import") (part "SJ2W"))
    )
    (comp (ref "SJ22")
      (value "SJ2W")
      (footprint "eagle-import:SJ_2")
      (libsource (lib "eagle-import") (part "SJ2W"))
    )
    (comp (ref "SJ23")
      (value "SJ")
      (footprint "eagle-import:SJ")
      (libsource (lib "eagle-import") (part "SJ"))
    )
    (comp (ref "SJ24")
      (value "SJ2W")
      (footprint "eagle-import:SJ_2")
      (libsource (lib "eagle-import") (part "SJ2W"))
    )
    (comp (ref "SJ25")
      (value "SJ")
      (footprint "eagle-import:SJ")
      (libsource (lib "eagle-import") (part "SJ"))
    )
    (comp (ref "SJ26")
      (value "SJ")
      (footprint "eagle-import:SJ")
      (libsource (lib "eagle-import") (part "SJ"))
    )
    (comp (ref "SJ27")
      (value "SJ2W")
      (footprint "eagle-import:SJ_2")
      (libsource (lib "eagle-import") (part "SJ2W"))
    )
    (comp (ref "SJ28")
      (value "SJ")
      (footprint "eagle-import:SJ")
      (libsource (lib "eagle-import") (part "SJ"))
    )
    (comp (ref "SJ29")
      (value "SJ2W")
      (footprint "eagle-import:SJ_2")
      (libsource (lib "eagle-import") (part "SJ2W"))
    )
    (comp (ref "SJ30")
      (value "SJ2W")
      (footprint "eagle-import:SJ_2")
      (libsource (lib "eagle-import") (part "SJ2W"))
    )
    (comp (ref "SJ31")
      (value "SJ")
      (footprint "eagle-import:SJ")
      (libsource (lib "eagle-import") (part "SJ"))
    )
    (comp (ref "SJ32")
      (value "SJ2W")
      (footprint "eagle-import:SJ_2")
      (libsource (lib "eagle-import") (part "SJ2W"))
    )
    (comp (ref "SJ33")
      (value "SJ")
      (footprint "eagle-import:SJ")
      (libsource (lib "eagle-import") (part "SJ"))
    )
    (comp (ref "SJ34")
      (value "SJ")
      (footprint "eagle-import:SJ")
      (libsource (lib "eagle-import") (part "SJ"))
    )
    (comp (ref "SJ35")
      (value "SJ")
      (footprint "eagle-import:SJ")
      (libsource (lib "eagle-import") (part "SJ"))
    )
    (comp (ref "TP1")
      (value "TPSB1,27")
      (footprint "eagle-import:B1,27")
      (libsource (lib "eagle-import") (part "TPSB1,27"))
    )
    (comp (ref "TP2")
      (value "TPSB1,27")
      (footprint "eagle-import:B1,27")
      (libsource (lib "eagle-import") (part "TPSB1,27"))
    )
    (comp (ref "TP3")
      (value "TPSB1,27")
      (footprint "eagle-import:B1,27")
      (libsource (lib "eagle-import") (part "TPSB1,27"))
    )
    (comp (ref "TP4")
      (value "TPSB1,27")
      (footprint "eagle-import:B1,27")
      (libsource (lib "eagle-import") (part "TPSB1,27"))
    )
    (comp (ref "TP5")
      (value "TPSB1,27")
      (footprint "eagle-import:B1,27")
      (libsource (lib "eagle-import") (part "TPSB1,27"))
    )
    (comp (ref "TP6")
      (value "TPSB1,27")
      (footprint "eagle-import:B1,27")
      (libsource (lib "eagle-import") (part "TPSB1,27"))
    )
    (comp (ref "TP8")
      (value "TPSB1,27")
      (footprint "eagle-import:B1,27")
      (libsource (lib "eagle-import") (part "TPSB1,27"))
    )
    (comp (ref "TP9")
      (value "TPSB1,27")
      (footprint "eagle-import:B1,27")
      (libsource (lib "eagle-import") (part "TPSB1,27"))
    )
    (comp (ref "TP10")
      (value "TPSB1,27")
      (footprint "eagle-import:B1,27")
      (libsource (lib "eagle-import") (part "TPSB1,27"))
    )
    (comp (ref "TP11")
      (value "TPSB1,27")
      (footprint "eagle-import:B1,27")
      (libsource (lib "eagle-import") (part "TPSB1,27"))
    )
    (comp (ref "TP12")
      (value "TPSB1,27")
      (footprint "eagle-import:B1,27")
      (libsource (lib "eagle-import") (part "TPSB1,27"))
    )
    (comp (ref "TP13")
      (value "TPSB1,27")
      (footprint "eagle-import:B1,27")
      (libsource (lib "eagle-import") (part "TPSB1,27"))
    )
    (comp (ref "TP14")
      (value "TPSB1,27")
      (footprint "eagle-import:B1,27")
      (libsource (lib "eagle-import") (part "TPSB1,27"))
    )
    (comp (ref "TP15")
      (value "TPSB1,27")
      (footprint "eagle-import:B1,27")
      (libsource (lib "eagle-import") (part "TPSB1,27"))
    )
    (comp (ref "TP16")
      (value "TPSB1,27")
      (footprint "eagle-import:B1,27")
      (libsource (lib "eagle-import") (part "TPSB1,27"))
    )
    (comp (ref "TP17")
      (value "TPSB1,27")
      (footprint "eagle-import:B1,27")
      (libsource (lib "eagle-import") (part "TPSB1,27"))
    )
    (comp (ref "TP18")
      (value "TPSB1,27")
      (footprint "eagle-import:B1,27")
      (libsource (lib "eagle-import") (part "TPSB1,27"))
    )
    (comp (ref "TP19")
      (value "TPSB1,27")
      (footprint "eagle-import:B1,27")
      (libsource (lib "eagle-import") (part "TPSB1,27"))
    )
    (comp (ref "TP20")
      (value "TPSB1,27")
      (footprint "eagle-import:B1,27")
      (libsource (lib "eagle-import") (part "TPSB1,27"))
    )
    (comp (ref "TP21")
      (value "TPSB1,27")
      (footprint "eagle-import:B1,27")
      (libsource (lib "eagle-import") (part "TPSB1,27"))
    )
    (comp (ref "TP22")
      (value "TPSB1,27")
      (footprint "eagle-import:B1,27")
      (libsource (lib "eagle-import") (part "TPSB1,27"))
    )
    (comp (ref "TP23")
      (value "TPSB1,27")
      (footprint "eagle-import:B1,27")
      (libsource (lib "eagle-import") (part "TPSB1,27"))
    )
    (comp (ref "TP24")
      (value "TPSB1,27")
      (footprint "eagle-import:B1,27")
      (libsource (lib "eagle-import") (part "TPSB1,27"))
    )
    (comp (ref "TP25")
      (value "TPSB1,27")
      (footprint "eagle-import:B1,27")
      (libsource (lib "eagle-import") (part "TPSB1,27"))
    )
    (comp (ref "TP26")
      (value "TPSB1,27")
      (footprint "eagle-import:B1,27")
      (libsource (lib "eagle-import") (part "TPSB1,27"))
    )
    (comp (ref "TP27")
      (value "TPSB1,27")
      (footprint "eagle-import:B1,27")
      (libsource (lib "eagle-import") (part "TPSB1,27"))
    )
    (comp (ref "TP28")
      (value "TPSB1,27")
      (footprint "eagle-import:B1,27")
      (libsource (lib "eagle-import") (part "TPSB1,27"))
    )
    (comp (ref "TP29")
      (value "TPSB1,27")
      (footprint "eagle-import:B1,27")
      (libsource (lib "eagle-import") (part "TPSB1,27"))
    )
    (comp (ref "TP30")
      (value "TPSB1,27")
      (footprint "eagle-import:B1,27")
      (libsource (lib "eagle-import") (part "TPSB1,27"))
    )
    (comp (ref "TP31")
      (value "TPSB1,27")
      (footprint "eagle-import:B1,27")
      (libsource (lib "eagle-import") (part "TPSB1,27"))
    )
    (comp (ref "U1")
      (value "AMS1117-2.5")
      (footprint "eagle-import:SOT229P700X180-4N")
      (fields (field (name "MF") "Advanced Monolithic Systems") (field (name "MP") "AMS1117-5.0"))
      (libsource (lib "eagle-import") (part "AMS1117-5.0"))
    )
    (comp (ref "U2")
      (value "AMS1117-3.3")
      (footprint "eagle-import:SOT229P700X180-4N")
      (fields (field (name "MF") "Advanced Monolithic Systems") (field (name "MP") "AMS1117-5.0"))
      (libsource (lib "eagle-import") (part "AMS1117-5.0"))
    )
    (comp (ref "U3")
      (value "AMS1117-5.0")
      (footprint "eagle-import:SOT229P700X180-4N")
      (fields (field (name "MF") "Advanced Monolithic Systems"))
      (libsource (lib "eagle-import") (part "AMS1117-5.0"))
    )
    (comp (ref "U4")
      (value "TMUX1111PWRTSSOP16")
      (footprint "eagle-import:SOP65P640X110-16N")
      (libsource (lib "eagle-import") (part "TMUX1111PWRTSSOP16"))
    )
    (comp (ref "U5")
      (value "REF5050IDR")
      (footprint "eagle-import:SOIC127P600X175-8N")
      (fields (field (name "MF") "Texas Instruments"))
      (libsource (lib "eagle-import") (part "REF5050IDR"))
    )
    (comp (ref "U6")
      (value "MAX4239AUT+T")
      (footprint "eagle-import:SOT23-6")
      (libsource (lib "eagle-import") (part "MAX4239AUT+T"))
    )
    (comp (ref "U7")
      (value "MAX4239AUT+T")
      (footprint "eagle-import:SOT23-6")
      (libsource (lib "eagle-import") (part "MAX4239AUT+T"))
    )
    (comp (ref "U8")
      (value "LTC2368IMS-16PBF")
      (footprint "eagle-import:MSOP-16_MS")
      (fields (field (name "MF") "Linear Technology") (field (name "MP") "LTC2368IMS-16#PBF"))
      (libsource (lib "eagle-import") (part "LTC2368IMS-16PBF"))
    )
    (comp (ref "U9")
      (value "ADS8681IPWR")
      (footprint "eagle-import:SOP65P640X120-16N")
      (libsource (lib "eagle-import") (part "ADS8681IPWR"))
    )
    (comp (ref "U10")
      (value "TPL0102-100PWRTSSOP14")
      (footprint "eagle-import:SOP65P640X120-14N")
      (libsource (lib "eagle-import") (part "TPL0102-100PWRTSSOP14"))
    )
    (comp (ref "U11")
      (value "MAX4239AUT+T")
      (footprint "eagle-import:SOT23-6")
      (libsource (lib "eagle-import") (part "MAX4239AUT+T"))
    )
    (comp (ref "U12")
      (value "ADUM3160")
      (footprint "eagle-import:SO16W")
      (fields (field (name "MF") "Analog Devices"))
      (libsource (lib "eagle-import") (part "ADUM3160"))
    )
    (comp (ref "X1")
      (value "DCBARRELPTH")
      (footprint "eagle-import:DCJACK_2MM_PTH")
      (libsource (lib "eagle-import") (part "DCBARRELPTH"))
    )
  )
  (nets
    (net (code "1") (name "+2V5") (class "Default")
      (node (ref "C21") (pin "1") (pinfunction "1_1") (pintype "passive"))
      (node (ref "C23") (pin "1") (pinfunction "1_1") (pintype "passive"))
      (node (ref "C8") (pin "+") (pinfunction "+_+") (pintype "passive"))
      (node (ref "D2") (pin "A") (pinfunction "A_A") (pintype "passive"))
      (node (ref "JP26") (pin "1") (pinfunction "1_1") (pintype "passive"))
      (node (ref "JP26") (pin "2") (pinfunction "2_2") (pintype "passive"))
      (node (ref "JP6") (pin "3") (pinfunction "3_3") (pintype "passive"))
      (node (ref "SJ4") (pin "3") (pinfunction "3_3") (pintype "passive"))
      (node (ref "SJ6") (pin "3") (pinfunction "3_3") (pintype "passive"))
      (node (ref "TP30") (pin "TP") (pinfunction "PP_TP") (pintype "input"))
      (node (ref "U1") (pin "2") (pinfunction "VOUT_2") (pintype "output"))
      (node (ref "U1") (pin "4") (pinfunction "VOUT_4") (pintype "output"))
      (node (ref "U8") (pin "2") (pinfunction "VDD_2") (pintype "power_in"))
    )
    (net (code "2") (name "+3V3") (class "Default")
      (node (ref "C35") (pin "1") (pinfunction "1_1") (pintype "passive"))
      (node (ref "C37") (pin "+") (pinfunction "+_+") (pintype "passive"))
      (node (ref "C49") (pin "1") (pinfunction "1_1") (pintype "passive"))
      (node (ref "C50") (pin "1") (pinfunction "1_1") (pintype "passive"))
      (node (ref "C9") (pin "+") (pinfunction "+_+") (pintype "passive"))
      (node (ref "D3") (pin "A") (pinfunction "A_A") (pintype "passive"))
      (node (ref "J2") (pin "4") (pinfunction "VDD_4") (pintype "bidirectional"))
      (node (ref "JP19") (pin "1") (pinfunction "1_1") (pintype "passive"))
      (node (ref "JP19") (pin "2") (pinfunction "2_2") (pintype "passive"))
      (node (ref "JP21") (pin "1") (pinfunction "1_1") (pintype "passive"))
      (node (ref "JP21") (pin "2") (pinfunction "2_2") (pintype "passive"))
      (node (ref "L1") (pin "2") (pinfunction "2_2") (pintype "passive"))
      (node (ref "L2") (pin "2") (pinfunction "2_2") (pintype "passive"))
      (node (ref "L3") (pin "2") (pinfunction "2_2") (pintype "passive"))
      (node (ref "R21") (pin "2") (pinfunction "2_2") (pintype "passive"))
      (node (ref "SJ13") (pin "3") (pinfunction "3_3") (pintype "passive"))
      (node (ref "SJ14") (pin "3") (pinfunction "3_3") (pintype "passive"))
      (node (ref "SJ15") (pin "3") (pinfunction "3_3") (pintype "passive"))
      (node (ref "SJ3") (pin "3") (pinfunction "3_3") (pintype "passive"))
      (node (ref "TP10") (pin "TP") (pinfunction "PP_TP") (pintype "input"))
      (node (ref "U10") (pin "14") (pinfunction "VDD_14") (pintype "power_in"))
      (node (ref "U2") (pin "2") (pinfunction "VOUT_2") (pintype "output"))
      (node (ref "U2") (pin "4") (pinfunction "VOUT_4") (pintype "output"))
    )
    (net (code "3") (name "+5V") (class "Default")
      (node (ref "C38") (pin "1") (pinfunction "1_1") (pintype "passive"))
      (node (ref "C39") (pin "1") (pinfunction "1_1") (pintype "passive"))
      (node (ref "C44") (pin "1") (pinfunction "1_1") (pintype "passive"))
      (node (ref "C45") (pin "1") (pinfunction "1_1") (pintype "passive"))
      (node (ref "C47") (pin "1") (pinfunction "1_1") (pintype "passive"))
      (node (ref "C48") (pin "1") (pinfunction "1_1") (pintype "passive"))
      (node (ref "IC1") (pin "5") (pinfunction "V+_5") (pintype "power_in"))
      (node (ref "J3") (pin "1") (pinfunction "VBUS_1") (pintype "bidirectional"))
      (node (ref "JP20") (pin "2") (pinfunction "2_2") (pintype "passive"))
      (node (ref "Q5") (pin "2") (pinfunction "S_2") (pintype "passive"))
      (node (ref "R18") (pin "1") (pinfunction "1_1") (pintype "passive"))
      (node (ref "SJ16") (pin "3") (pinfunction "3_3") (pintype "passive"))
      (node (ref "SJ22") (pin "1") (pinfunction "1_1") (pintype "passive"))
      (node (ref "TP28") (pin "TP") (pinfunction "PP_TP") (pintype "input"))
      (node (ref "U11") (pin "5") (pinfunction "~{CS}_5") (pintype "input"))
      (node (ref "U11") (pin "6") (pinfunction "V+_6") (pintype "power_in"))
      (node (ref "U12") (pin "16") (pinfunction "VBUS2_16") (pintype "power_in"))
    )
    (net (code "4") (name "+5V{slash}1") (class "Default")
      (node (ref "C40") (pin "1") (pinfunction "1_1") (pintype "passive"))
      (node (ref "C42") (pin "1") (pinfunction "1_1") (pintype "passive"))
      (node (ref "J1") (pin "1") (pinfunction "VBUS_1") (pintype "passive"))
      (node (ref "SJ28") (pin "2") (pinfunction "2_2") (pintype "passive"))
      (node (ref "TP21") (pin "TP") (pinfunction "PP_TP") (pintype "input"))
      (node (ref "U12") (pin "1") (pinfunction "VBUS1_1") (pintype "power_in"))
    )
    (net (code "5") (name "+DC_OUT_VAR") (class "Default")
      (node (ref "JP9") (pin "4") (pinfunction "4_4") (pintype "passive"))
      (node (ref "Q6") (pin "2") (pinfunction "S_2") (pintype "passive"))
      (node (ref "SJ16") (pin "1") (pinfunction "1_1") (pintype "passive"))
      (node (ref "SJ22") (pin "3") (pinfunction "3_3") (pintype "passive"))
      (node (ref "SJ25") (pin "1") (pinfunction "1_1") (pintype "passive"))
      (node (ref "SJ8") (pin "1") (pinfunction "1_1") (pintype "passive"))
    )
    (net (code "6") (name "/CURR_MEAS_POS") (class "Default")
      (node (ref "JP3") (pin "1") (pinfunction "1_1") (pintype "passive"))
      (node (ref "PAD1") (pin "1") (pinfunction "P_1") (pintype "passive"))
      (node (ref "PAD3") (pin "1") (pinfunction "P_1") (pintype "passive"))
      (node (ref "Q2") (pin "2") (pinfunction "S_2") (pintype "passive"))
      (node (ref "Q4") (pin "2") (pinfunction "S_2") (pintype "passive"))
      (node (ref "R2") (pin "1") (pinfunction "1_1") (pintype "passive"))
      (node (ref "TP4") (pin "TP") (pinfunction "PP_TP") (pintype "input"))
      (node (ref "U4") (pin "7") (pinfunction "D4_7") (pintype "passive"))
    )
    (net (code "7") (name "/CURR_SRC_OUT") (class "Default")
      (node (ref "JP12") (pin "1") (pinfunction "1_1") (pintype "passive"))
      (node (ref "PAD5") (pin "1") (pinfunction "P_1") (pintype "passive"))
      (node (ref "PAD7") (pin "1") (pinfunction "P_1") (pintype "passive"))
      (node (ref "R22") (pin "1") (pinfunction "1_1") (pintype "passive"))
      (node (ref "R24") (pin "1") (pinfunction "1_1") (pintype "passive"))
      (node (ref "SJ25") (pin "2") (pinfunction "2_2") (pintype "passive"))
    )
    (net (code "8") (name "AGND") (class "Default")
      (node (ref "C1") (pin "-") (pinfunction "-_-") (pintype "passive"))
      (node (ref "C11") (pin "2") (pinfunction "2_2") (pintype "passive"))
      (node (ref "C12") (pin "2") (pinfunction "2_2") (pintype "passive"))
      (node (ref "C13") (pin "2") (pinfunction "2_2") (pintype "passive"))
      (node (ref "C15") (pin "2") (pinfunction "2_2") (pintype "passive"))
      (node (ref "C16") (pin "2") (pinfunction "2_2") (pintype "passive"))
      (node (ref "C18") (pin "2") (pinfunction "2_2") (pintype "passive"))
      (node (ref "C19") (pin "2") (pinfunction "2_2") (pintype "passive"))
      (node (ref "C2") (pin "2") (pinfunction "2_2") (pintype "passive"))
      (node (ref "C20") (pin "2") (pinfunction "2_2") (pintype "passive"))
      (node (ref "C21") (pin "2") (pinfunction "2_2") (pintype "passive"))
      (node (ref "C23") (pin "2") (pinfunction "2_2") (pintype "passive"))
      (node (ref "C24") (pin "2") (pinfunction "2_2") (pintype "passive"))
      (node (ref "C25") (pin "2") (pinfunction "2_2") (pintype "passive"))
      (node (ref "C26") (pin "2") (pinfunction "2_2") (pintype "passive"))
      (node (ref "C27") (pin "2") (pinfunction "2_2") (pintype "passive"))
      (node (ref "C28") (pin "2") (pinfunction "2_2") (pintype "passive"))
      (node (ref "C29") (pin "2") (pinfunction "2_2") (pintype "passive"))
      (node (ref "C3") (pin "-") (pinfunction "-_-") (pintype "passive"))
      (node (ref "C30") (pin "2") (pinfunction "2_2") (pintype "passive"))
      (node (ref "C31") (pin "2") (pinfunction "2_2") (pintype "passive"))
      (node (ref "C32") (pin "2") (pinfunction "2_2") (pintype "passive"))
      (node (ref "C33") (pin "2") (pinfunction "2_2") (pintype "passive"))
      (node (ref "C34") (pin "2") (pinfunction "2_2") (pintype "passive"))
      (node (ref "C36") (pin "2") (pinfunction "2_2") (pintype "passive"))
      (node (ref "C4") (pin "-") (pinfunction "-_-") (pintype "passive"))
      (node (ref "C5") (pin "-") (pinfunction "-_-") (pintype "passive"))
      (node (ref "C6") (pin "2") (pinfunction "2_2") (pintype "passive"))
      (node (ref "C7") (pin "2") (pinfunction "2_2") (pintype "passive"))
      (node (ref "JP1") (pin "2") (pinfunction "2_2") (pintype "passive"))
      (node (ref "JP17") (pin "1") (pinfunction "1_1") (pintype "passive"))
      (node (ref "JP22") (pin "1") (pinfunction "1_1") (pintype "passive"))
      (node (ref "JP24") (pin "1") (pinfunction "1_1") (pintype "passive"))
      (node (ref "JP4") (pin "1") (pinfunction "1_1") (pintype "passive"))
      (node (ref "JP5") (pin "2") (pinfunction "2_2") (pintype "passive"))
      (node (ref "JP6") (pin "2") (pinfunction "2_2") (pintype "passive"))
      (node (ref "JP8") (pin "1") (pinfunction "1_1") (pintype "passive"))
      (node (ref "PAD2") (pin "1") (pinfunction "P_1") (pintype "passive"))
      (node (ref "PAD4") (pin "1") (pinfunction "P_1") (pintype "passive"))
      (node (ref "Q1") (pin "1") (pinfunction "G_1") (pintype "passive"))
      (node (ref "R1") (pin "1") (pinfunction "1_1") (pintype "passive"))
      (node (ref "R11") (pin "1") (pinfunction "1_1") (pintype "passive"))
      (node (ref "R14") (pin "2") (pinfunction "2_2") (pintype "passive"))
      (node (ref "R2") (pin "2") (pinfunction "2_2") (pintype "passive"))
      (node (ref "R3") (pin "2") (pinfunction "2_2") (pintype "passive"))
      (node (ref "R5") (pin "E1") (pinfunction "E1_E1") (pintype "passive"))
      (node (ref "R5") (pin "I1") (pinfunction "I1_I1") (pintype "passive"))
      (node (ref "R6") (pin "2") (pinfunction "2_2") (pintype "passive"))
      (node (ref "R7") (pin "2") (pinfunction "2_2") (pintype "passive"))
      (node (ref "R8") (pin "2") (pinfunction "2_2") (pintype "passive"))
      (node (ref "SJ1") (pin "2") (pinfunction "2_2") (pintype "passive"))
      (node (ref "SJ19") (pin "3") (pinfunction "3_3") (pintype "passive"))
      (node (ref "SJ2") (pin "2") (pinfunction "2_2") (pintype "passive"))
      (node (ref "SJ24") (pin "3") (pinfunction "3_3") (pintype "passive"))
      (node (ref "SJ3") (pin "1") (pinfunction "1_1") (pintype "passive"))
      (node (ref "SJ5") (pin "3") (pinfunction "3_3") (pintype "passive"))
      (node (ref "SJ7") (pin "3") (pinfunction "3_3") (pintype "passive"))
      (node (ref "TP2") (pin "TP") (pinfunction "PP_TP") (pintype "input"))
      (node (ref "TP3") (pin "TP") (pinfunction "PP_TP") (pintype "input"))
      (node (ref "U1") (pin "1") (pinfunction "ADJ/GND_1") (pintype "power_in"))
      (node (ref "U2") (pin "1") (pinfunction "ADJ/GND_1") (pintype "power_in"))
      (node (ref "U3") (pin "1") (pinfunction "ADJ/GND_1") (pintype "power_in"))
      (node (ref "U4") (pin "5") (pinfunction "GND_5") (pintype "passive"))
      (node (ref "U5") (pin "4") (pinfunction "GND_4") (pintype "passive"))
      (node (ref "U8") (pin "10") (pinfunction "GND_10") (pintype "power_in"))
      (node (ref "U8") (pin "16") (pinfunction "GND_16") (pintype "power_in"))
      (node (ref "U8") (pin "3") (pinfunction "GND_3") (pintype "power_in"))
      (node (ref "U8") (pin "5") (pinfunction "IN-_5") (pintype "input"))
      (node (ref "U8") (pin "6") (pinfunction "GND_6") (pintype "power_in"))
      (node (ref "U9") (pin "1") (pinfunction "DGND_1") (pintype "power_in"))
      (node (ref "U9") (pin "3") (pinfunction "AGND_3") (pintype "power_in"))
      (node (ref "U9") (pin "5") (pinfunction "REFGND_5") (pintype "power_in"))
      (node (ref "U9") (pin "8") (pinfunction "AIN_GND_8") (pintype "input"))
      (node (ref "X1") (pin "GND") (pinfunction "GND_GND") (pintype "power_in"))
      (node (ref "X1") (pin "GNDBREAK") (pinfunction "GNDBREAK_GNDBREAK") (pintype "power_in"))
    )
    (net (code "9") (name "ASW-1") (class "Default")
      (node (ref "JP14") (pin "3") (pinfunction "3_3") (pintype "passive"))
      (node (ref "SJ3") (pin "2") (pinfunction "2_2") (pintype "passive"))
      (node (ref "U4") (pin "1") (pinfunction "SEL1_1") (pintype "input"))
    )
    (net (code "10") (name "ASW-2") (class "Default")
      (node (ref "JP14") (pin "4") (pinfunction "4_4") (pintype "passive"))
      (node (ref "U4") (pin "16") (pinfunction "SEL2_16") (pintype "input"))
    )
    (net (code "11") (name "ASW-3") (class "Default")
      (node (ref "JP14") (pin "5") (pinfunction "5_5") (pintype "passive"))
      (node (ref "U4") (pin "9") (pinfunction "SEL3_9") (pintype "input"))
    )
    (net (code "12") (name "ASW-4") (class "Default")
      (node (ref "JP14") (pin "6") (pinfunction "6_6") (pintype "passive"))
      (node (ref "U4") (pin "8") (pinfunction "SEL4_8") (pintype "input"))
    )
    (net (code "13") (name "BUSY_ADC2") (class "Default")
      (node (ref "JP16") (pin "2") (pinfunction "2_2") (pintype "passive"))
      (node (ref "U8") (pin "11") (pinfunction "BUSY_11") (pintype "passive"))
    )
    (net (code "14") (name "CHAIN_ADC2") (class "Default")
      (node (ref "JP16") (pin "1") (pinfunction "1_1") (pintype "passive"))
      (node (ref "SJ19") (pin "2") (pinfunction "2_2") (pintype "passive"))
      (node (ref "U8") (pin "1") (pinfunction "CHAIN_1") (pintype "input"))
    )
    (net (code "15") (name "CNV_ADC2") (class "Default")
      (node (ref "JP16") (pin "3") (pinfunction "3_3") (pintype "passive"))
      (node (ref "U8") (pin "9") (pinfunction "CNV_9") (pintype "input"))
    )
    (net (code "16") (name "CS_ADC1") (class "Default")
      (node (ref "JP15") (pin "3") (pinfunction "3_3") (pintype "passive"))
      (node (ref "U9") (pin "11") (pinfunction "CONVST/CS_11") (pintype "bidirectional"))
    )
    (net (code "17") (name "D+_USB_EXT") (class "Default")
      (node (ref "J1") (pin "3") (pinfunction "D+_3") (pintype "passive"))
      (node (ref "R29") (pin "1") (pinfunction "1_1") (pintype "passive"))
      (node (ref "TP25") (pin "TP") (pinfunction "PP_TP") (pintype "input"))
    )
    (net (code "18") (name "D+_USB_INT") (class "Default")
      (node (ref "J3") (pin "3") (pinfunction "D+_3") (pintype "bidirectional"))
      (node (ref "JP18") (pin "1") (pinfunction "1_1") (pintype "passive"))
      (node (ref "R34") (pin "2") (pinfunction "2_2") (pintype "passive"))
      (node (ref "TP26") (pin "TP") (pinfunction "PP_TP") (pintype "input"))
    )
    (net (code "19") (name "D-_USB_EXT") (class "Default")
      (node (ref "J1") (pin "2") (pinfunction "D-_2") (pintype "passive"))
      (node (ref "R27") (pin "1") (pinfunction "1_1") (pintype "passive"))
      (node (ref "TP24") (pin "TP") (pinfunction "PP_TP") (pintype "input"))
    )
    (net (code "20") (name "D-_USB_INT") (class "Default")
      (node (ref "J3") (pin "2") (pinfunction "D-_2") (pintype "bidirectional"))
      (node (ref "JP18") (pin "2") (pinfunction "2_2") (pintype "passive"))
      (node (ref "R33") (pin "2") (pinfunction "2_2") (pintype "passive"))
      (node (ref "TP27") (pin "TP") (pinfunction "PP_TP") (pintype "input"))
    )
    (net (code "21") (name "GND") (class "Default")
      (node (ref "BT1") (pin "2") (pinfunction "-_2") (pintype "passive"))
      (node (ref "C22") (pin "-") (pinfunction "-_-") (pintype "passive"))
      (node (ref "C35") (pin "2") (pinfunction "2_2") (pintype "passive"))
      (node (ref "C37") (pin "-") (pinfunction "-_-") (pintype "passive"))
      (node (ref "C38") (pin "2") (pinfunction "2_2") (pintype "passive"))
      (node (ref "C39") (pin "2") (pinfunction "2_2") (pintype "passive"))
      (node (ref "C41") (pin "2") (pinfunction "2_2") (pintype "passive"))
      (node (ref "C44") (pin "2") (pinfunction "2_2") (pintype "passive"))
      (node (ref "C45") (pin "2") (pinfunction "2_2") (pintype "passive"))
      (node (ref "C46") (pin "2") (pinfunction "2_2") (pintype "passive"))
      (node (ref "C47") (pin "2") (pinfunction "2_2") (pintype "passive"))
      (node (ref "C48") (pin "2") (pinfunction "2_2") (pintype "passive"))
      (node (ref "C49") (pin "2") (pinfunction "2_2") (pintype "passive"))
      (node (ref "C50") (pin "2") (pinfunction "2_2") (pintype "passive"))
      (node (ref "IC1") (pin "2") (pinfunction "V-_2") (pintype "power_in"))
      (node (ref "J2") (pin "3") (pinfunction "VSS1_3") (pintype "bidirectional"))
      (node (ref "J2") (pin "6") (pinfunction "VSS2_6") (pintype "bidirectional"))
      (node (ref "J2") (pin "GND1") (pinfunction "GND_GND1") (pintype "bidirectional"))
      (node (ref "J2") (pin "GND2") (pinfunction "GND_GND2") (pintype "bidirectional"))
      (node (ref "J2") (pin "GND3") (pinfunction "GND_GND3") (pintype "bidirectional"))
      (node (ref "J2") (pin "GND4") (pinfunction "GND_GND4") (pintype "bidirectional"))
      (node (ref "J3") (pin "4") (pinfunction "GND_4") (pintype "bidirectional"))
      (node (ref "J3") (pin "SHELL") (pinfunction "SHIELD_SHELL") (pintype "bidirectional"))
      (node (ref "J3") (pin "SHELL1") (pinfunction "SHIELD_SHELL1") (pintype "bidirectional"))
      (node (ref "JP10") (pin "2") (pinfunction "2_2") (pintype "passive"))
      (node (ref "JP13") (pin "1") (pinfunction "1_1") (pintype "passive"))
      (node (ref "JP17") (pin "2") (pinfunction "2_2") (pintype "passive"))
      (node (ref "JP22") (pin "2") (pinfunction "2_2") (pintype "passive"))
      (node (ref "JP24") (pin "2") (pinfunction "2_2") (pintype "passive"))
      (node (ref "JP25") (pin "8") (pinfunction "8_8") (pintype "passive"))
      (node (ref "JP9") (pin "3") (pinfunction "3_3") (pintype "passive"))
      (node (ref "PAD6") (pin "1") (pinfunction "P_1") (pintype "passive"))
      (node (ref "PAD8") (pin "1") (pinfunction "P_1") (pintype "passive"))
      (node (ref "R20") (pin "2") (pinfunction "2_2") (pintype "passive"))
      (node (ref "R25") (pin "2") (pinfunction "2_2") (pintype "passive"))
      (node (ref "R30") (pin "1") (pinfunction "1_1") (pintype "passive"))
      (node (ref "SJ13") (pin "1") (pinfunction "1_1") (pintype "passive"))
      (node (ref "SJ14") (pin "1") (pinfunction "1_1") (pintype "passive"))
      (node (ref "SJ15") (pin "1") (pinfunction "1_1") (pintype "passive"))
      (node (ref "SJ18") (pin "1") (pinfunction "1_1") (pintype "passive"))
      (node (ref "SJ21") (pin "3") (pinfunction "3_3") (pintype "passive"))
      (node (ref "SJ30") (pin "3") (pinfunction "3_3") (pintype "passive"))
      (node (ref "SJ32") (pin "3") (pinfunction "3_3") (pintype "passive"))
      (node (ref "SJ33") (pin "2") (pinfunction "2_2") (pintype "passive"))
      (node (ref "SJ35") (pin "2") (pinfunction "2_2") (pintype "passive"))
      (node (ref "TP29") (pin "TP") (pinfunction "PP_TP") (pintype "input"))
      (node (ref "U10") (pin "11") (pinfunction "GND_11") (pintype "power_in"))
      (node (ref "U10") (pin "8") (pinfunction "VSS_8") (pintype "power_in"))
      (node (ref "U11") (pin "2") (pinfunction "V-_2") (pintype "power_in"))
      (node (ref "U12") (pin "15") (pinfunction "GND2_15") (pintype "power_in"))
      (node (ref "U12") (pin "9") (pinfunction "GND2_9") (pintype "power_in"))
    )
    (net (code "22") (name "GND_USB") (class "Default")
      (node (ref "C40") (pin "2") (pinfunction "2_2") (pintype "passive"))
      (node (ref "C42") (pin "2") (pinfunction "2_2") (pintype "passive"))
      (node (ref "C43") (pin "2") (pinfunction "2_2") (pintype "passive"))
      (node (ref "J1") (pin "5") (pinfunction "GND_5") (pintype "passive"))
      (node (ref "J1") (pin "SHELL") (pinfunction "SHIELD_SHELL") (pintype "passive"))
      (node (ref "J1") (pin "SHELL1") (pinfunction "SHIELD_SHELL1") (pintype "passive"))
      (node (ref "J1") (pin "SHELL2") (pinfunction "SHIELD_SHELL2") (pintype "passive"))
      (node (ref "J1") (pin "SHELL3") (pinfunction "SHIELD_SHELL3") (pintype "passive"))
      (node (ref "SJ26") (pin "2") (pinfunction "2_2") (pintype "passive"))
      (node (ref "SJ27") (pin "1") (pinfunction "1_1") (pintype "passive"))
      (node (ref "SJ29") (pin "1") (pinfunction "1_1") (pintype "passive"))
      (node (ref "TP22") (pin "TP") (pinfunction "PP_TP") (pintype "input"))
      (node (ref "U12") (pin "2") (pinfunction "GND1_2") (pintype "power_in"))
      (node (ref "U12") (pin "8") (pinfunction "GND1_8") (pintype "power_in"))
    )
    (net (code "23") (name "Net-(C8-Pad-)") (class "Default")
      (node (ref "C8") (pin "-") (pinfunction "-_-") (pintype "passive"))
      (node (ref "R6") (pin "1") (pinfunction "1_1") (pintype "passive"))
    )
    (net (code "24") (name "Net-(C9-Pad-)") (class "Default")
      (node (ref "C9") (pin "-") (pinfunction "-_-") (pintype "passive"))
      (node (ref "R7") (pin "1") (pinfunction "1_1") (pintype "passive"))
    )
    (net (code "25") (name "Net-(C10-Pad-)") (class "Default")
      (node (ref "C10") (pin "-") (pinfunction "-_-") (pintype "passive"))
      (node (ref "R8") (pin "1") (pinfunction "1_1") (pintype "passive"))
    )
    (net (code "26") (name "Net-(C13-Pad1)") (class "Default")
      (node (ref "C13") (pin "1") (pinfunction "1_1") (pintype "passive"))
      (node (ref "R9") (pin "2") (pinfunction "2_2") (pintype "passive"))
    )
    (net (code "27") (name "Net-(C20-Pad1)") (class "Default")
      (node (ref "C20") (pin "1") (pinfunction "1_1") (pintype "passive"))
      (node (ref "SJ11") (pin "2") (pinfunction "2_2") (pintype "passive"))
    )
    (net (code "28") (name "Net-(IC1-+IN)") (class "Default")
      (node (ref "IC1") (pin "1") (pinfunction "+IN_1") (pintype "input"))
      (node (ref "R28") (pin "2") (pinfunction "2_2") (pintype "passive"))
    )
    (net (code "29") (name "Net-(IC1-OUT)") (class "Default")
      (node (ref "IC1") (pin "4") (pinfunction "OUT_4") (pintype "output"))
      (node (ref "Q6") (pin "1") (pinfunction "G_1") (pintype "passive"))
      (node (ref "R30") (pin "2") (pinfunction "2_2") (pintype "passive"))
      (node (ref "TP20") (pin "TP") (pinfunction "PP_TP") (pintype "input"))
    )
    (net (code "30") (name "Net-(J1-ID)") (class "Default")
      (node (ref "J1") (pin "4") (pinfunction "ID_4") (pintype "passive"))
      (node (ref "SJ26") (pin "1") (pinfunction "1_1") (pintype "passive"))
    )
    (net (code "31") (name "Net-(J2-CLK)") (class "Default")
      (node (ref "J2") (pin "5") (pinfunction "CLK_5") (pintype "bidirectional"))
      (node (ref "JP27") (pin "3") (pinfunction "3_3") (pintype "passive"))
    )
    (net (code "32") (name "Net-(J2-CMD)") (class "Default")
      (node (ref "J2") (pin "2") (pinfunction "CMD_2") (pintype "bidirectional"))
      (node (ref "JP27") (pin "2") (pinfunction "2_2") (pintype "passive"))
    )
    (net (code "33") (name "Net-(J2-DAT0)") (class "Default")
      (node (ref "J2") (pin "7") (pinfunction "DAT0_7") (pintype "bidirectional"))
      (node (ref "JP27") (pin "4") (pinfunction "4_4") (pintype "passive"))
    )
    (net (code "34") (name "Net-(J2-DAT1)") (class "Default")
      (node (ref "J2") (pin "8") (pinfunction "DAT1_8") (pintype "bidirectional"))
      (node (ref "JP27") (pin "5") (pinfunction "5_5") (pintype "passive"))
    )
    (net (code "35") (name "Net-(J2-DAT2)") (class "Default")
      (node (ref "J2") (pin "9") (pinfunction "DAT2_9") (pintype "bidirectional"))
      (node (ref "JP27") (pin "6") (pinfunction "6_6") (pintype "passive"))
    )
    (net (code "36") (name "Net-(J2-DAT3)") (class "Default")
      (node (ref "J2") (pin "1") (pinfunction "DAT3_1") (pintype "bidirectional"))
      (node (ref "JP27") (pin "1") (pinfunction "1_1") (pintype "passive"))
    )
    (net (code "37") (name "Net-(J2-PadCD)") (class "Default")
      (node (ref "J2") (pin "CD") (pinfunction "CD_CD") (pintype "bidirectional"))
      (node (ref "JP27") (pin "7") (pinfunction "7_7") (pintype "passive"))
    )
    (net (code "38") (name "Net-(J2-PadWP)") (class "Default")
      (node (ref "J2") (pin "WP") (pinfunction "WP_WP") (pintype "bidirectional"))
      (node (ref "JP27") (pin "8") (pinfunction "8_8") (pintype "passive"))
    )
    (net (code "39") (name "Net-(JP25-Pad5)") (class "Default")
      (node (ref "JP25") (pin "5") (pinfunction "5_5") (pintype "passive"))
      (node (ref "R31") (pin "2") (pinfunction "2_2") (pintype "passive"))
      (node (ref "R32") (pin "1") (pinfunction "1_1") (pintype "passive"))
      (node (ref "SJ31") (pin "2") (pinfunction "2_2") (pintype "passive"))
    )
    (net (code "40") (name "Net-(JP25-Pad7)") (class "Default")
      (node (ref "JP25") (pin "7") (pinfunction "7_7") (pintype "passive"))
      (node (ref "R35") (pin "2") (pinfunction "2_2") (pintype "passive"))
      (node (ref "R36") (pin "1") (pinfunction "1_1") (pintype "passive"))
      (node (ref "SJ34") (pin "2") (pinfunction "2_2") (pintype "passive"))
    )
    (net (code "41") (name "Net-(LED1-PadC)") (class "Default")
      (node (ref "LED1") (pin "C") (pinfunction "C_C") (pintype "passive"))
      (node (ref "R1") (pin "2") (pinfunction "2_2") (pintype "passive"))
    )
    (net (code "42") (name "Net-(Q1-D)") (class "Default")
      (node (ref "D1") (pin "C") (pinfunction "C_C") (pintype "passive"))
      (node (ref "F1") (pin "1") (pinfunction "1_1") (pintype "passive"))
      (node (ref "Q1") (pin "3") (pinfunction "D_3") (pintype "passive"))
    )
    (net (code "43") (name "Net-(Q1-S)") (class "Default")
      (node (ref "D1") (pin "A") (pinfunction "A_A") (pintype "passive"))
      (node (ref "JP2") (pin "2") (pinfunction "2_2") (pintype "passive"))
      (node (ref "Q1") (pin "2") (pinfunction "S_2") (pintype "passive"))
    )
    (net (code "44") (name "Net-(Q2-D)") (class "Default")
      (node (ref "Q2") (pin "3") (pinfunction "D_3") (pintype "passive"))
      (node (ref "R3") (pin "1") (pinfunction "1_1") (pintype "passive"))
      (node (ref "TP6") (pin "TP") (pinfunction "PP_TP") (pintype "input"))
      (node (ref "U4") (pin "10") (pinfunction "D3_10") (pintype "passive"))
    )
    (net (code "45") (name "Net-(Q3-B)") (class "Default")
      (node (ref "C2") (pin "1") (pinfunction "1_1") (pintype "passive"))
      (node (ref "Q3") (pin "4") (pinfunction "B_4") (pintype "passive"))
      (node (ref "R4") (pin "2") (pinfunction "2_2") (pintype "passive"))
    )
    (net (code "46") (name "Net-(Q4-D)") (class "Default")
      (node (ref "Q4") (pin "3") (pinfunction "D_3") (pintype "passive"))
      (node (ref "R5") (pin "I2") (pinfunction "I2_I2") (pintype "passive"))
    )
    (net (code "47") (name "Net-(Q5-D)") (class "Default")
      (node (ref "Q5") (pin "3") (pinfunction "D_3") (pintype "passive"))
      (node (ref "R20") (pin "1") (pinfunction "1_1") (pintype "passive"))
      (node (ref "SJ12") (pin "1") (pinfunction "1_1") (pintype "passive"))
      (node (ref "SJ9") (pin "2") (pinfunction "2_2") (pintype "passive"))
    )
    (net (code "48") (name "Net-(Q6-D)") (class "Default")
      (node (ref "Q6") (pin "3") (pinfunction "D_3") (pintype "passive"))
      (node (ref "R22") (pin "2") (pinfunction "2_2") (pintype "passive"))
      (node (ref "R23") (pin "1") (pinfunction "1_1") (pintype "passive"))
    )
    (net (code "49") (name "Net-(R12-Pad2)") (class "Default")
      (node (ref "R12") (pin "2") (pinfunction "2_2") (pintype "passive"))
      (node (ref "R13") (pin "1") (pinfunction "1_1") (pintype "passive"))
    )
    (net (code "50") (name "Net-(R15-Pad1)") (class "Default")
      (node (ref "R15") (pin "1") (pinfunction "1_1") (pintype "passive"))
      (node (ref "R16") (pin "2") (pinfunction "2_2") (pintype "passive"))
    )
    (net (code "51") (name "Net-(R32-Pad2)") (class "Default")
      (node (ref "R32") (pin "2") (pinfunction "2_2") (pintype "passive"))
      (node (ref "SJ33") (pin "1") (pinfunction "1_1") (pintype "passive"))
    )
    (net (code "52") (name "Net-(R36-Pad2)") (class "Default")
      (node (ref "R36") (pin "2") (pinfunction "2_2") (pintype "passive"))
      (node (ref "SJ35") (pin "1") (pinfunction "1_1") (pintype "passive"))
    )
    (net (code "53") (name "Net-(TP1-PP)") (class "Default")
      (node (ref "JP1") (pin "1") (pinfunction "1_1") (pintype "passive"))
      (node (ref "JP2") (pin "1") (pinfunction "1_1") (pintype "passive"))
      (node (ref "TP1") (pin "TP") (pinfunction "PP_TP") (pintype "input"))
      (node (ref "X1") (pin "PWR") (pinfunction "PWR_PWR") (pintype "power_in"))
    )
    (net (code "54") (name "Net-(TP8-PP)") (class "Default")
      (node (ref "R5") (pin "E2") (pinfunction "E2_E2") (pintype "passive"))
      (node (ref "TP8") (pin "TP") (pinfunction "PP_TP") (pintype "input"))
      (node (ref "U4") (pin "15") (pinfunction "D2_15") (pintype "passive"))
    )
    (net (code "55") (name "Net-(TP9-PP)") (class "Default")
      (node (ref "TP9") (pin "TP") (pinfunction "PP_TP") (pintype "input"))
      (node (ref "U5") (pin "3") (pinfunction "TEMP_3") (pintype "input"))
    )
    (net (code "56") (name "Net-(TP13-PP)") (class "Default")
      (node (ref "R10") (pin "1") (pinfunction "1_1") (pintype "passive"))
      (node (ref "TP13") (pin "TP") (pinfunction "PP_TP") (pintype "input"))
      (node (ref "U4") (pin "11") (pinfunction "S3_11") (pintype "passive"))
      (node (ref "U4") (pin "14") (pinfunction "S2_14") (pintype "passive"))
      (node (ref "U4") (pin "6") (pinfunction "S4_6") (pintype "passive"))
    )
    (net (code "57") (name "Net-(TP14-PP)") (class "Default")
      (node (ref "C14") (pin "2") (pinfunction "2_2") (pintype "passive"))
      (node (ref "R13") (pin "2") (pinfunction "2_2") (pintype "passive"))
      (node (ref "TP14") (pin "TP") (pinfunction "PP_TP") (pintype "input"))
      (node (ref "U6") (pin "1") (pinfunction "OUT_1") (pintype "output"))
      (node (ref "U7") (pin "3") (pinfunction "+IN_3") (pintype "input"))
    )
    (net (code "58") (name "Net-(TP15-PP)") (class "Default")
      (node (ref "R17") (pin "2") (pinfunction "2_2") (pintype "passive"))
      (node (ref "R19") (pin "1") (pinfunction "1_1") (pintype "passive"))
      (node (ref "SJ10") (pin "2") (pinfunction "2_2") (pintype "passive"))
      (node (ref "TP15") (pin "TP") (pinfunction "PP_TP") (pintype "input"))
    )
    (net (code "59") (name "Net-(TP17-PP)") (class "Default")
      (node (ref "SJ17") (pin "1") (pinfunction "1_1") (pintype "passive"))
      (node (ref "SJ18") (pin "3") (pinfunction "3_3") (pintype "passive"))
      (node (ref "TP17") (pin "TP") (pinfunction "PP_TP") (pintype "input"))
      (node (ref "U10") (pin "3") (pinfunction "WA_3") (pintype "passive"))
    )
    (net (code "60") (name "Net-(TP18-PP)") (class "Default")
      (node (ref "C36") (pin "1") (pinfunction "1_1") (pintype "passive"))
      (node (ref "JP11") (pin "2") (pinfunction "2_2") (pintype "passive"))
      (node (ref "SJ20") (pin "1") (pinfunction "1_1") (pintype "passive"))
      (node (ref "TP18") (pin "TP") (pinfunction "PP_TP") (pintype "input"))
      (node (ref "U9") (pin "4") (pinfunction "REFIO_4") (pintype "bidirectional"))
    )
    (net (code "61") (name "Net-(TP23-PP)") (class "Default")
      (node (ref "R26") (pin "1") (pinfunction "1_1") (pintype "passive"))
      (node (ref "R28") (pin "1") (pinfunction "1_1") (pintype "passive"))
      (node (ref "TP23") (pin "TP") (pinfunction "PP_TP") (pintype "input"))
      (node (ref "U11") (pin "1") (pinfunction "OUT_1") (pintype "output"))
    )
    (net (code "62") (name "Net-(TP31-PP)") (class "Default")
      (node (ref "C3") (pin "+") (pinfunction "+_+") (pintype "passive"))
      (node (ref "C4") (pin "+") (pinfunction "+_+") (pintype "passive"))
      (node (ref "C5") (pin "+") (pinfunction "+_+") (pintype "passive"))
      (node (ref "D2") (pin "C") (pinfunction "C_C") (pintype "passive"))
      (node (ref "D3") (pin "C") (pinfunction "C_C") (pintype "passive"))
      (node (ref "D4") (pin "C") (pinfunction "C_C") (pintype "passive"))
      (node (ref "Q3") (pin "1") (pinfunction "E_1") (pintype "passive"))
      (node (ref "Q3") (pin "2") (pinfunction "E_2") (pintype "passive"))
      (node (ref "Q3") (pin "3") (pinfunction "E_3") (pintype "passive"))
      (node (ref "TP31") (pin "TP") (pinfunction "PP_TP") (pintype "input"))
      (node (ref "U1") (pin "3") (pinfunction "VIN_3") (pintype "input"))
      (node (ref "U2") (pin "3") (pinfunction "VIN_3") (pintype "input"))
      (node (ref "U3") (pin "3") (pinfunction "VIN_3") (pintype "input"))
    )
    (net (code "63") (name "Net-(U4-D1)") (class "Default")
      (node (ref "SJ1") (pin "1") (pinfunction "1_1") (pintype "passive"))
      (node (ref "U4") (pin "2") (pinfunction "D1_2") (pintype "passive"))
    )
    (net (code "64") (name "Net-(U4-S1)") (class "Default")
      (node (ref "SJ2") (pin "1") (pinfunction "1_1") (pintype "passive"))
      (node (ref "U4") (pin "3") (pinfunction "S1_3") (pintype "passive"))
    )
    (net (code "65") (name "Net-(U4-VCC)") (class "Default")
      (node (ref "C11") (pin "1") (pinfunction "1_1") (pintype "passive"))
      (node (ref "C12") (pin "1") (pinfunction "1_1") (pintype "passive"))
      (node (ref "L1") (pin "1") (pinfunction "1_1") (pintype "passive"))
      (node (ref "U4") (pin "13") (pinfunction "VCC_13") (pintype "power_in"))
    )
    (net (code "66") (name "Net-(U5-TRIM{slash}NR)") (class "Default")
      (node (ref "C7") (pin "1") (pinfunction "1_1") (pintype "passive"))
      (node (ref "U5") (pin "5") (pinfunction "TRIM/NR_5") (pintype "input"))
    )
    (net (code "67") (name "Net-(U6-+IN)") (class "Default")
      (node (ref "R10") (pin "2") (pinfunction "2_2") (pintype "passive"))
      (node (ref "U6") (pin "3") (pinfunction "+IN_3") (pintype "input"))
    )
    (net (code "68") (name "Net-(U6--IN)") (class "Default")
      (node (ref "C14") (pin "1") (pinfunction "1_1") (pintype "passive"))
      (node (ref "R11") (pin "2") (pinfunction "2_2") (pintype "passive"))
      (node (ref "R12") (pin "1") (pinfunction "1_1") (pintype "passive"))
      (node (ref "U6") (pin "4") (pinfunction "-IN_4") (pintype "input"))
    )
    (net (code "69") (name "Net-(U6-V+)") (class "Default")
      (node (ref "C15") (pin "1") (pinfunction "1_1") (pintype "passive"))
      (node (ref "C16") (pin "1") (pinfunction "1_1") (pintype "passive"))
      (node (ref "SJ4") (pin "2") (pinfunction "2_2") (pintype "passive"))
      (node (ref "U6") (pin "5") (pinfunction "~{CS}_5") (pintype "input"))
      (node (ref "U6") (pin "6") (pinfunction "V+_6") (pintype "power_in"))
    )
    (net (code "70") (name "Net-(U6-V-)") (class "Default")
      (node (ref "SJ5") (pin "2") (pinfunction "2_2") (pintype "passive"))
      (node (ref "U6") (pin "2") (pinfunction "V-_2") (pintype "power_in"))
    )
    (net (code "71") (name "Net-(U7--IN)") (class "Default")
      (node (ref "C17") (pin "1") (pinfunction "1_1") (pintype "passive"))
      (node (ref "R14") (pin "1") (pinfunction "1_1") (pintype "passive"))
      (node (ref "R15") (pin "2") (pinfunction "2_2") (pintype "passive"))
      (node (ref "U7") (pin "4") (pinfunction "-IN_4") (pintype "input"))
    )
    (net (code "72") (name "Net-(U7-OUT)") (class "Default")
      (node (ref "C17") (pin "2") (pinfunction "2_2") (pintype "passive"))
      (node (ref "R16") (pin "1") (pinfunction "1_1") (pintype "passive"))
      (node (ref "R17") (pin "1") (pinfunction "1_1") (pintype "passive"))
      (node (ref "U7") (pin "1") (pinfunction "OUT_1") (pintype "output"))
    )
    (net (code "73") (name "Net-(U7-V+)") (class "Default")
      (node (ref "C18") (pin "1") (pinfunction "1_1") (pintype "passive"))
      (node (ref "C19") (pin "1") (pinfunction "1_1") (pintype "passive"))
      (node (ref "SJ6") (pin "2") (pinfunction "2_2") (pintype "passive"))
      (node (ref "U7") (pin "5") (pinfunction "~{CS}_5") (pintype "input"))
      (node (ref "U7") (pin "6") (pinfunction "V+_6") (pintype "power_in"))
    )
    (net (code "74") (name "Net-(U7-V-)") (class "Default")
      (node (ref "SJ7") (pin "2") (pinfunction "2_2") (pintype "passive"))
      (node (ref "U7") (pin "2") (pinfunction "V-_2") (pintype "power_in"))
    )
    (net (code "75") (name "Net-(U8-OVDD)") (class "Default")
      (node (ref "C25") (pin "1") (pinfunction "1_1") (pintype "passive"))
      (node (ref "C27") (pin "1") (pinfunction "1_1") (pintype "passive"))
      (node (ref "L2") (pin "1") (pinfunction "1_1") (pintype "passive"))
      (node (ref "SJ19") (pin "1") (pinfunction "1_1") (pintype "passive"))
      (node (ref "SJ24") (pin "1") (pinfunction "1_1") (pintype "passive"))
      (node (ref "U8") (pin "15") (pinfunction "OVDD_15") (pintype "power_in"))
    )
    (net (code "76") (name "Net-(U9-DVDD)") (class "Default")
      (node (ref "C30") (pin "1") (pinfunction "1_1") (pintype "passive"))
      (node (ref "C31") (pin "1") (pinfunction "1_1") (pintype "passive"))
      (node (ref "C32") (pin "1") (pinfunction "1_1") (pintype "passive"))
      (node (ref "L3") (pin "1") (pinfunction "1_1") (pintype "passive"))
      (node (ref "U9") (pin "16") (pinfunction "DVDD_16") (pintype "power_in"))
    )
    (net (code "77") (name "Net-(U9-REFCAP)") (class "Default")
      (node (ref "C33") (pin "1") (pinfunction "1_1") (pintype "passive"))
      (node (ref "C34") (pin "1") (pinfunction "1_1") (pintype "passive"))
      (node (ref "U9") (pin "6") (pinfunction "REFCAP_6") (pintype "bidirectional"))
    )
    (net (code "78") (name "Net-(U10-A0)") (class "Default")
      (node (ref "SJ13") (pin "2") (pinfunction "2_2") (pintype "passive"))
      (node (ref "U10") (pin "13") (pinfunction "A0_13") (pintype "input"))
    )
    (net (code "79") (name "Net-(U10-A1)") (class "Default")
      (node (ref "SJ14") (pin "2") (pinfunction "2_2") (pintype "passive"))
      (node (ref "U10") (pin "12") (pinfunction "A1_12") (pintype "input"))
    )
    (net (code "80") (name "Net-(U10-A2)") (class "Default")
      (node (ref "SJ15") (pin "2") (pinfunction "2_2") (pintype "passive"))
      (node (ref "U10") (pin "7") (pinfunction "A2_7") (pintype "input"))
    )
    (net (code "81") (name "Net-(U10-HA)") (class "Default")
      (node (ref "SJ16") (pin "2") (pinfunction "2_2") (pintype "passive"))
      (node (ref "U10") (pin "1") (pinfunction "HA_1") (pintype "passive"))
    )
    (net (code "82") (name "Net-(U10-HB)") (class "Default")
      (node (ref "SJ22") (pin "2") (pinfunction "2_2") (pintype "passive"))
      (node (ref "U10") (pin "4") (pinfunction "HB_4") (pintype "passive"))
    )
    (net (code "83") (name "Net-(U10-LA)") (class "Default")
      (node (ref "SJ18") (pin "2") (pinfunction "2_2") (pintype "passive"))
      (node (ref "U10") (pin "2") (pinfunction "LA_2") (pintype "passive"))
    )
    (net (code "84") (name "Net-(U10-LB)") (class "Default")
      (node (ref "SJ21") (pin "2") (pinfunction "2_2") (pintype "passive"))
      (node (ref "U10") (pin "5") (pinfunction "LB_5") (pintype "passive"))
    )
    (net (code "85") (name "Net-(U11-+IN)") (class "Default")
      (node (ref "R23") (pin "2") (pinfunction "2_2") (pintype "passive"))
      (node (ref "R25") (pin "1") (pinfunction "1_1") (pintype "passive"))
      (node (ref "U11") (pin "3") (pinfunction "+IN_3") (pintype "input"))
    )
    (net (code "86") (name "Net-(U11--IN)") (class "Default")
      (node (ref "R24") (pin "2") (pinfunction "2_2") (pintype "passive"))
      (node (ref "R26") (pin "2") (pinfunction "2_2") (pintype "passive"))
      (node (ref "U11") (pin "4") (pinfunction "-IN_4") (pintype "input"))
    )
    (net (code "87") (name "Net-(U12-DD+)") (class "Default")
      (node (ref "R34") (pin "1") (pinfunction "1_1") (pintype "passive"))
      (node (ref "U12") (pin "10") (pinfunction "DD+_10") (pintype "bidirectional"))
    )
    (net (code "88") (name "Net-(U12-DD-)") (class "Default")
      (node (ref "R33") (pin "1") (pinfunction "1_1") (pintype "passive"))
      (node (ref "U12") (pin "11") (pinfunction "DD-_11") (pintype "bidirectional"))
    )
    (net (code "89") (name "Net-(U12-PDEN)") (class "Default")
      (node (ref "SJ29") (pin "2") (pinfunction "2_2") (pintype "passive"))
      (node (ref "U12") (pin "4") (pinfunction "PDEN_4") (pintype "input"))
    )
    (net (code "90") (name "Net-(U12-PIN)") (class "Default")
      (node (ref "SJ30") (pin "2") (pinfunction "2_2") (pintype "passive"))
      (node (ref "U12") (pin "12") (pinfunction "PIN_12") (pintype "input"))
    )
    (net (code "91") (name "Net-(U12-SPD)") (class "Default")
      (node (ref "SJ32") (pin "2") (pinfunction "2_2") (pintype "passive"))
      (node (ref "U12") (pin "13") (pinfunction "SPD_13") (pintype "input"))
    )
    (net (code "92") (name "Net-(U12-SPU)") (class "Default")
      (node (ref "SJ27") (pin "2") (pinfunction "2_2") (pintype "passive"))
      (node (ref "U12") (pin "5") (pinfunction "SPU_5") (pintype "input"))
    )
    (net (code "93") (name "Net-(U12-UD+)") (class "Default")
      (node (ref "R29") (pin "2") (pinfunction "2_2") (pintype "passive"))
      (node (ref "U12") (pin "7") (pinfunction "UD+_7") (pintype "bidirectional"))
    )
    (net (code "94") (name "Net-(U12-UD-)") (class "Default")
      (node (ref "R27") (pin "2") (pinfunction "2_2") (pintype "passive"))
      (node (ref "U12") (pin "6") (pinfunction "UD-_6") (pintype "bidirectional"))
    )
    (net (code "95") (name "PSU_EN") (class "Default")
      (node (ref "JP9") (pin "1") (pinfunction "1_1") (pintype "passive"))
      (node (ref "SJ12") (pin "2") (pinfunction "2_2") (pintype "passive"))
    )
    (net (code "96") (name "PSU_EN_CONTROL") (class "Default")
      (node (ref "JP25") (pin "6") (pinfunction "6_6") (pintype "passive"))
      (node (ref "Q5") (pin "1") (pinfunction "G_1") (pintype "passive"))
      (node (ref "R18") (pin "2") (pinfunction "2_2") (pintype "passive"))
      (node (ref "SJ9") (pin "1") (pinfunction "1_1") (pintype "passive"))
    )
    (net (code "97") (name "PSU_I_CONTROL") (class "Default")
      (node (ref "C41") (pin "1") (pinfunction "1_1") (pintype "passive"))
      (node (ref "IC1") (pin "3") (pinfunction "-IN_3") (pintype "input"))
      (node (ref "JP25") (pin "3") (pinfunction "3_3") (pintype "passive"))
      (node (ref "SJ23") (pin "1") (pinfunction "1_1") (pintype "passive"))
    )
    (net (code "98") (name "PSU_I_SENSE") (class "Default")
      (node (ref "R35") (pin "1") (pinfunction "1_1") (pintype "passive"))
      (node (ref "SJ21") (pin "1") (pinfunction "1_1") (pintype "passive"))
      (node (ref "SJ23") (pin "2") (pinfunction "2_2") (pintype "passive"))
      (node (ref "SJ34") (pin "1") (pinfunction "1_1") (pintype "passive"))
      (node (ref "TP19") (pin "TP") (pinfunction "PP_TP") (pintype "input"))
      (node (ref "U10") (pin "6") (pinfunction "WB_6") (pintype "passive"))
    )
    (net (code "99") (name "PSU_U_CONTROL") (class "Default")
      (node (ref "JP25") (pin "1") (pinfunction "1_1") (pintype "passive"))
      (node (ref "JP9") (pin "5") (pinfunction "5_5") (pintype "passive"))
      (node (ref "SJ17") (pin "2") (pinfunction "2_2") (pintype "passive"))
    )
    (net (code "100") (name "PSU_U_SENSE") (class "Default")
      (node (ref "R31") (pin "1") (pinfunction "1_1") (pintype "passive"))
      (node (ref "SJ31") (pin "1") (pinfunction "1_1") (pintype "passive"))
      (node (ref "SJ8") (pin "2") (pinfunction "2_2") (pintype "passive"))
    )
    (net (code "101") (name "RANGE_MA") (class "Default")
      (node (ref "JP14") (pin "1") (pinfunction "1_1") (pintype "passive"))
      (node (ref "Q4") (pin "1") (pinfunction "G_1") (pintype "passive"))
    )
    (net (code "102") (name "RANGE_UA") (class "Default")
      (node (ref "JP14") (pin "2") (pinfunction "2_2") (pintype "passive"))
      (node (ref "Q2") (pin "1") (pinfunction "G_1") (pintype "passive"))
    )
    (net (code "103") (name "RST_ADC1") (class "Default")
      (node (ref "JP15") (pin "2") (pinfunction "2_2") (pintype "passive"))
      (node (ref "R21") (pin "1") (pinfunction "1_1") (pintype "passive"))
      (node (ref "U9") (pin "9") (pinfunction "RST_9") (pintype "bidirectional"))
    )
    (net (code "104") (name "RVS_ADC1") (class "Default")
      (node (ref "JP15") (pin "1") (pinfunction "1_1") (pintype "passive"))
      (node (ref "U9") (pin "15") (pinfunction "RVS_15") (pintype "bidirectional"))
    )
    (net (code "105") (name "SCK_ADC2") (class "Default")
      (node (ref "JP16") (pin "4") (pinfunction "4_4") (pintype "passive"))
      (node (ref "U8") (pin "13") (pinfunction "SCK_13") (pintype "input"))
    )
    (net (code "106") (name "SCL") (class "Default")
      (node (ref "JP25") (pin "2") (pinfunction "2_2") (pintype "passive"))
      (node (ref "U10") (pin "10") (pinfunction "SCL_10") (pintype "input"))
    )
    (net (code "107") (name "SCLK_ADC1") (class "Default")
      (node (ref "JP15") (pin "4") (pinfunction "4_4") (pintype "passive"))
      (node (ref "U9") (pin "12") (pinfunction "SCLK_12") (pintype "bidirectional"))
    )
    (net (code "108") (name "SDA") (class "Default")
      (node (ref "JP25") (pin "4") (pinfunction "4_4") (pintype "passive"))
      (node (ref "U10") (pin "9") (pinfunction "SDA_9") (pintype "bidirectional"))
    )
    (net (code "109") (name "SDI_ADC1") (class "Default")
      (node (ref "JP15") (pin "5") (pinfunction "5_5") (pintype "passive"))
      (node (ref "U9") (pin "10") (pinfunction "SDI_10") (pintype "bidirectional"))
    )
    (net (code "110") (name "SDI_ADC2") (class "Default")
      (node (ref "JP16") (pin "5") (pinfunction "5_5") (pintype "passive"))
      (node (ref "SJ24") (pin "2") (pinfunction "2_2") (pintype "passive"))
      (node (ref "U8") (pin "12") (pinfunction "RDL/SDI_12") (pintype "input"))
    )
    (net (code "111") (name "SDO-0_ADC1") (class "Default")
      (node (ref "JP15") (pin "6") (pinfunction "6_6") (pintype "passive"))
      (node (ref "U9") (pin "13") (pinfunction "SDO-0_13") (pintype "bidirectional"))
    )
    (net (code "112") (name "SDO-1_ADC1") (class "Default")
      (node (ref "JP15") (pin "7") (pinfunction "7_7") (pintype "passive"))
      (node (ref "U9") (pin "14") (pinfunction "ALARM/SDO-1/GPO_14") (pintype "bidirectional"))
    )
    (net (code "113") (name "SDO_ADC2") (class "Default")
      (node (ref "JP16") (pin "6") (pinfunction "6_6") (pintype "passive"))
      (node (ref "U8") (pin "14") (pinfunction "SDO_14") (pintype "output"))
    )
    (net (code "114") (name "TOADC") (class "Default")
      (node (ref "JP7") (pin "1") (pinfunction "1_1") (pintype "passive"))
      (node (ref "R19") (pin "2") (pinfunction "2_2") (pintype "passive"))
      (node (ref "SJ10") (pin "1") (pinfunction "1_1") (pintype "passive"))
      (node (ref "SJ11") (pin "1") (pinfunction "1_1") (pintype "passive"))
      (node (ref "TP16") (pin "TP") (pinfunction "PP_TP") (pintype "input"))
      (node (ref "U8") (pin "4") (pinfunction "IN+_4") (pintype "input"))
      (node (ref "U9") (pin "7") (pinfunction "AIN_P_7") (pintype "input"))
    )
    (net (code "115") (name "VBAT") (class "Default")
      (node (ref "BT1") (pin "1") (pinfunction "+_1") (pintype "passive"))
      (node (ref "JP10") (pin "1") (pinfunction "1_1") (pintype "passive"))
    )
    (net (code "116") (name "VDD") (class "Default")
      (node (ref "C10") (pin "+") (pinfunction "+_+") (pintype "passive"))
      (node (ref "C24") (pin "1") (pinfunction "1_1") (pintype "passive"))
      (node (ref "C26") (pin "1") (pinfunction "1_1") (pintype "passive"))
      (node (ref "C28") (pin "1") (pinfunction "1_1") (pintype "passive"))
      (node (ref "C6") (pin "1") (pinfunction "1_1") (pintype "passive"))
      (node (ref "D4") (pin "A") (pinfunction "A_A") (pintype "passive"))
      (node (ref "JP20") (pin "1") (pinfunction "1_1") (pintype "passive"))
      (node (ref "JP23") (pin "1") (pinfunction "1_1") (pintype "passive"))
      (node (ref "JP23") (pin "2") (pinfunction "2_2") (pintype "passive"))
      (node (ref "SJ4") (pin "1") (pinfunction "1_1") (pintype "passive"))
      (node (ref "SJ6") (pin "1") (pinfunction "1_1") (pintype "passive"))
      (node (ref "TP11") (pin "TP") (pinfunction "PP_TP") (pintype "input"))
      (node (ref "U3") (pin "2") (pinfunction "VOUT_2") (pintype "output"))
      (node (ref "U3") (pin "4") (pinfunction "VOUT_4") (pintype "output"))
      (node (ref "U5") (pin "2") (pinfunction "VIN_2") (pintype "input"))
      (node (ref "U9") (pin "2") (pinfunction "AVDD_2") (pintype "power_in"))
    )
    (net (code "117") (name "VDD1") (class "Default")
      (node (ref "C43") (pin "1") (pinfunction "1_1") (pintype "passive"))
      (node (ref "SJ27") (pin "3") (pinfunction "3_3") (pintype "passive"))
      (node (ref "SJ28") (pin "1") (pinfunction "1_1") (pintype "passive"))
      (node (ref "SJ29") (pin "3") (pinfunction "3_3") (pintype "passive"))
      (node (ref "U12") (pin "3") (pinfunction "VDD1_3") (pintype "power_in"))
    )
    (net (code "118") (name "VDD2") (class "Default")
      (node (ref "C46") (pin "1") (pinfunction "1_1") (pintype "passive"))
      (node (ref "SJ30") (pin "1") (pinfunction "1_1") (pintype "passive"))
      (node (ref "SJ32") (pin "1") (pinfunction "1_1") (pintype "passive"))
      (node (ref "U12") (pin "14") (pinfunction "VDD2_14") (pintype "power_in"))
    )
    (net (code "119") (name "VIN") (class "Default")
      (node (ref "C1") (pin "+") (pinfunction "+_+") (pintype "passive"))
      (node (ref "C22") (pin "+") (pinfunction "+_+") (pintype "passive"))
      (node (ref "F1") (pin "2") (pinfunction "2_2") (pintype "passive"))
      (node (ref "JP5") (pin "1") (pinfunction "1_1") (pintype "passive"))
      (node (ref "JP9") (pin "2") (pinfunction "2_2") (pintype "passive"))
      (node (ref "LED1") (pin "A") (pinfunction "A_A") (pintype "passive"))
      (node (ref "Q3") (pin "5") (pinfunction "C_5") (pintype "passive"))
      (node (ref "R4") (pin "1") (pinfunction "1_1") (pintype "passive"))
      (node (ref "TP5") (pin "TP") (pinfunction "PP_TP") (pintype "input"))
    )
    (net (code "120") (name "VREF_EXT") (class "Default")
      (node (ref "C29") (pin "1") (pinfunction "1_1") (pintype "passive"))
      (node (ref "JP11") (pin "1") (pinfunction "1_1") (pintype "passive"))
      (node (ref "R9") (pin "1") (pinfunction "1_1") (pintype "passive"))
      (node (ref "SJ20") (pin "2") (pinfunction "2_2") (pintype "passive"))
      (node (ref "TP12") (pin "TP") (pinfunction "PP_TP") (pintype "input"))
      (node (ref "U5") (pin "6") (pinfunction "VOUT_6") (pintype "output"))
      (node (ref "U8") (pin "7") (pinfunction "REF_2_7") (pintype "input"))
      (node (ref "U8") (pin "8") (pinfunction "REF_8") (pintype "input"))
    )
    (net (code "121") (name "VSS") (class "Default")
      (node (ref "JP6") (pin "1") (pinfunction "1_1") (pintype "passive"))
      (node (ref "SJ5") (pin "1") (pinfunction "1_1") (pintype "passive"))
      (node (ref "SJ7") (pin "1") (pinfunction "1_1") (pintype "passive"))
    )
    (net (code "122") (name "unconnected-(U5-DNC(1)-Pad8)") (class "Default")
      (node (ref "U5") (pin "8") (pinfunction "DNC(1)_8") (pintype "no_connect"))
    )
    (net (code "123") (name "unconnected-(U5-DNC(1)_2-Pad1)") (class "Default")
      (node (ref "U5") (pin "1") (pinfunction "DNC(1)_2_1") (pintype "no_connect"))
    )
    (net (code "124") (name "unconnected-(U5-NC(2)-Pad7)") (class "Default")
      (node (ref "U5") (pin "7") (pinfunction "NC(2)_7") (pintype "no_connect"))
    )
  )
)
